# controller.net
KiCad netlist of a schematic drawn in EAGLE
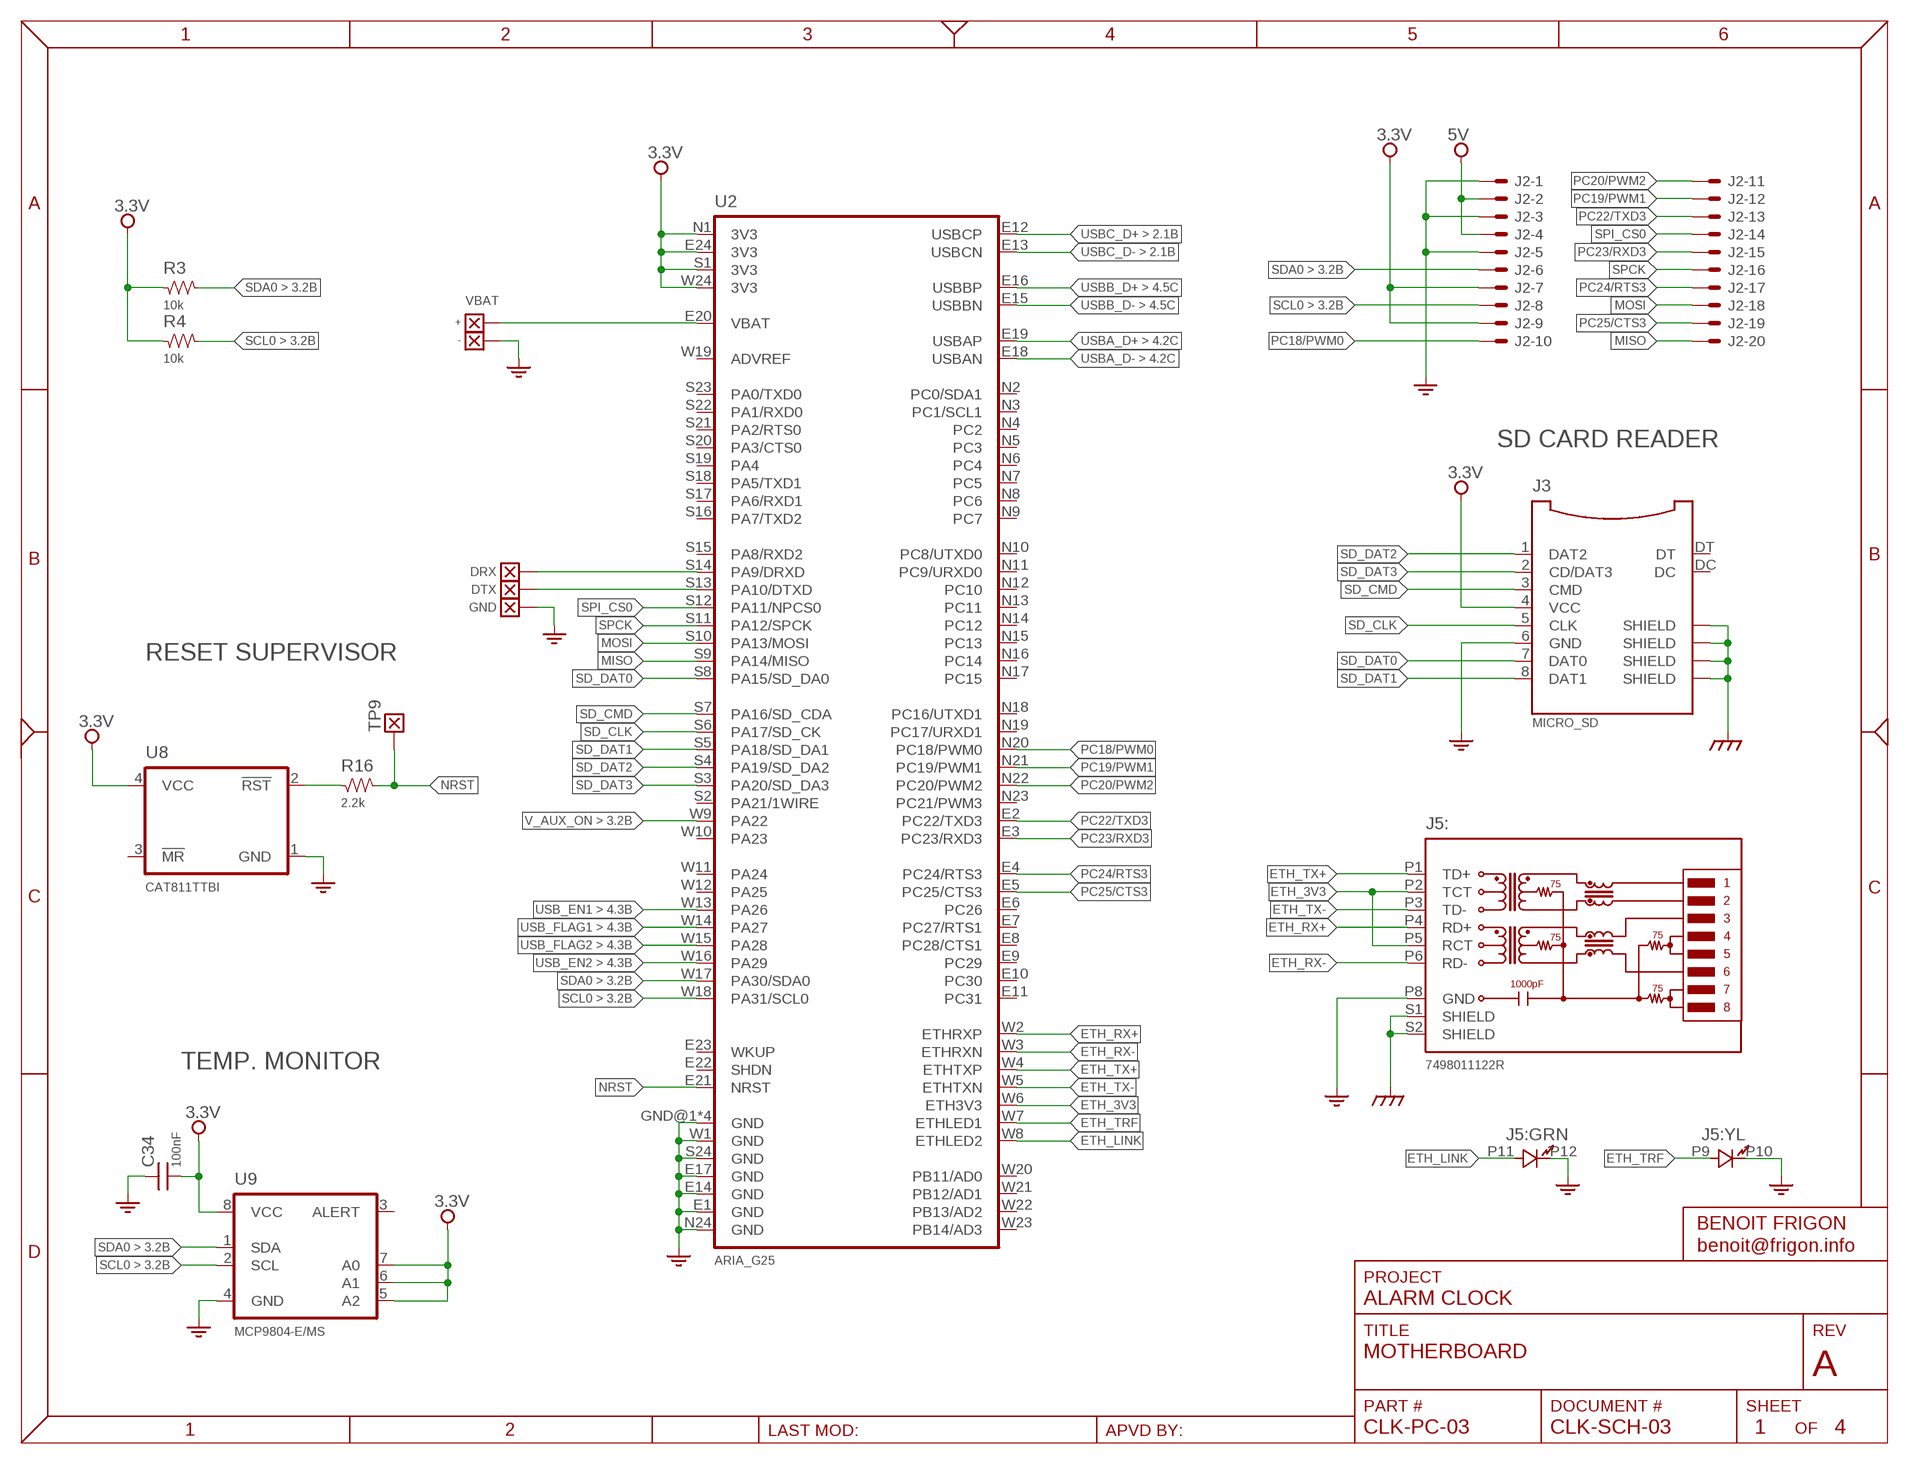
[diagram p0: schematic, sheet 1]
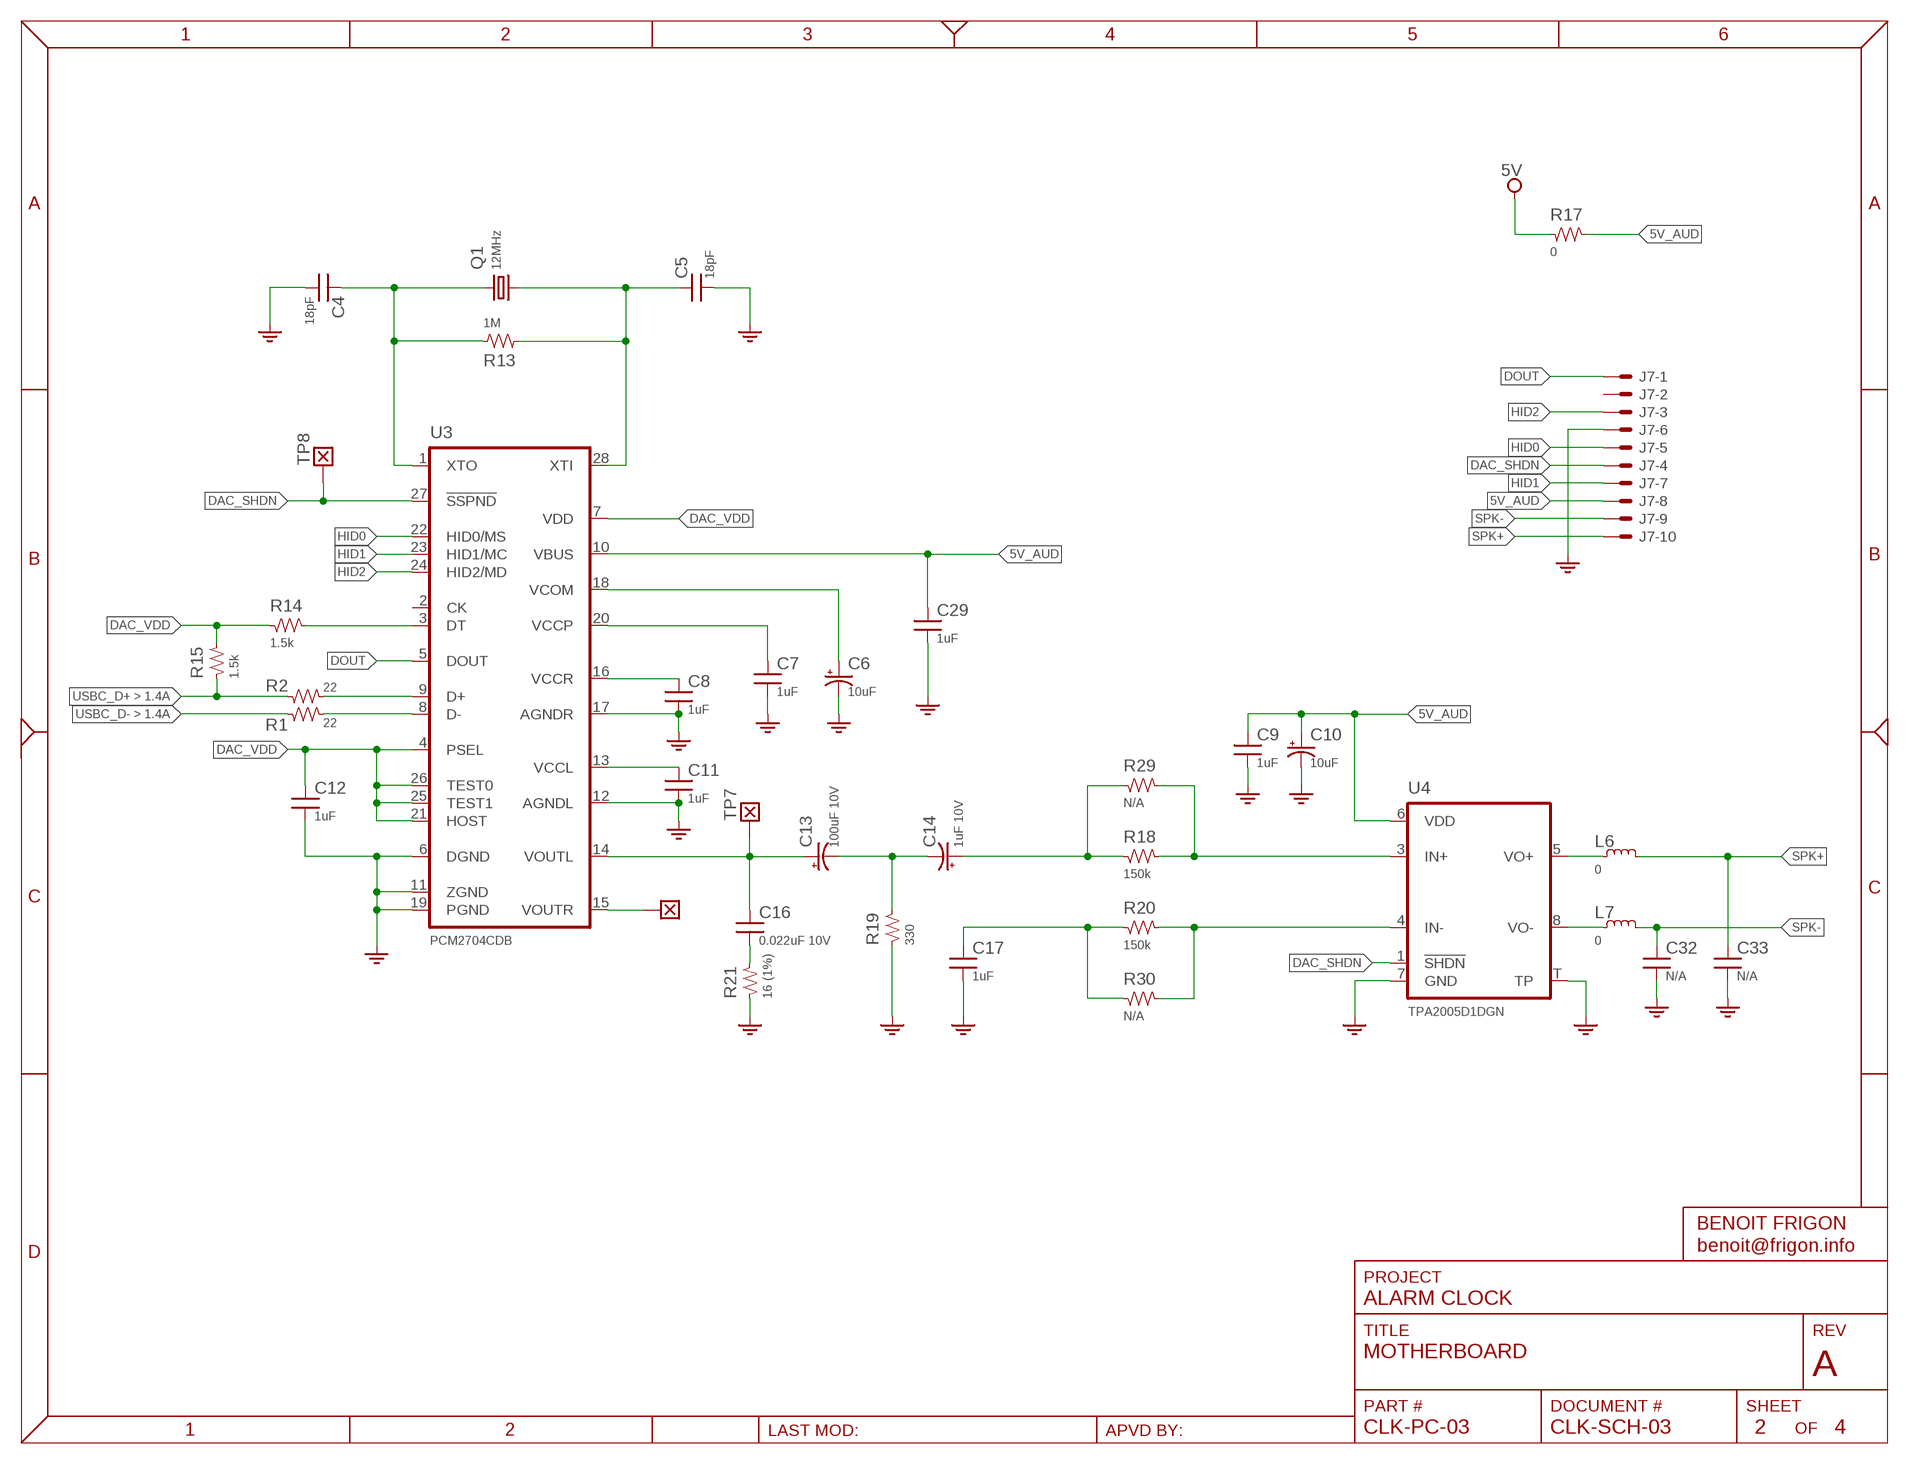
[diagram p1: schematic, sheet 2]
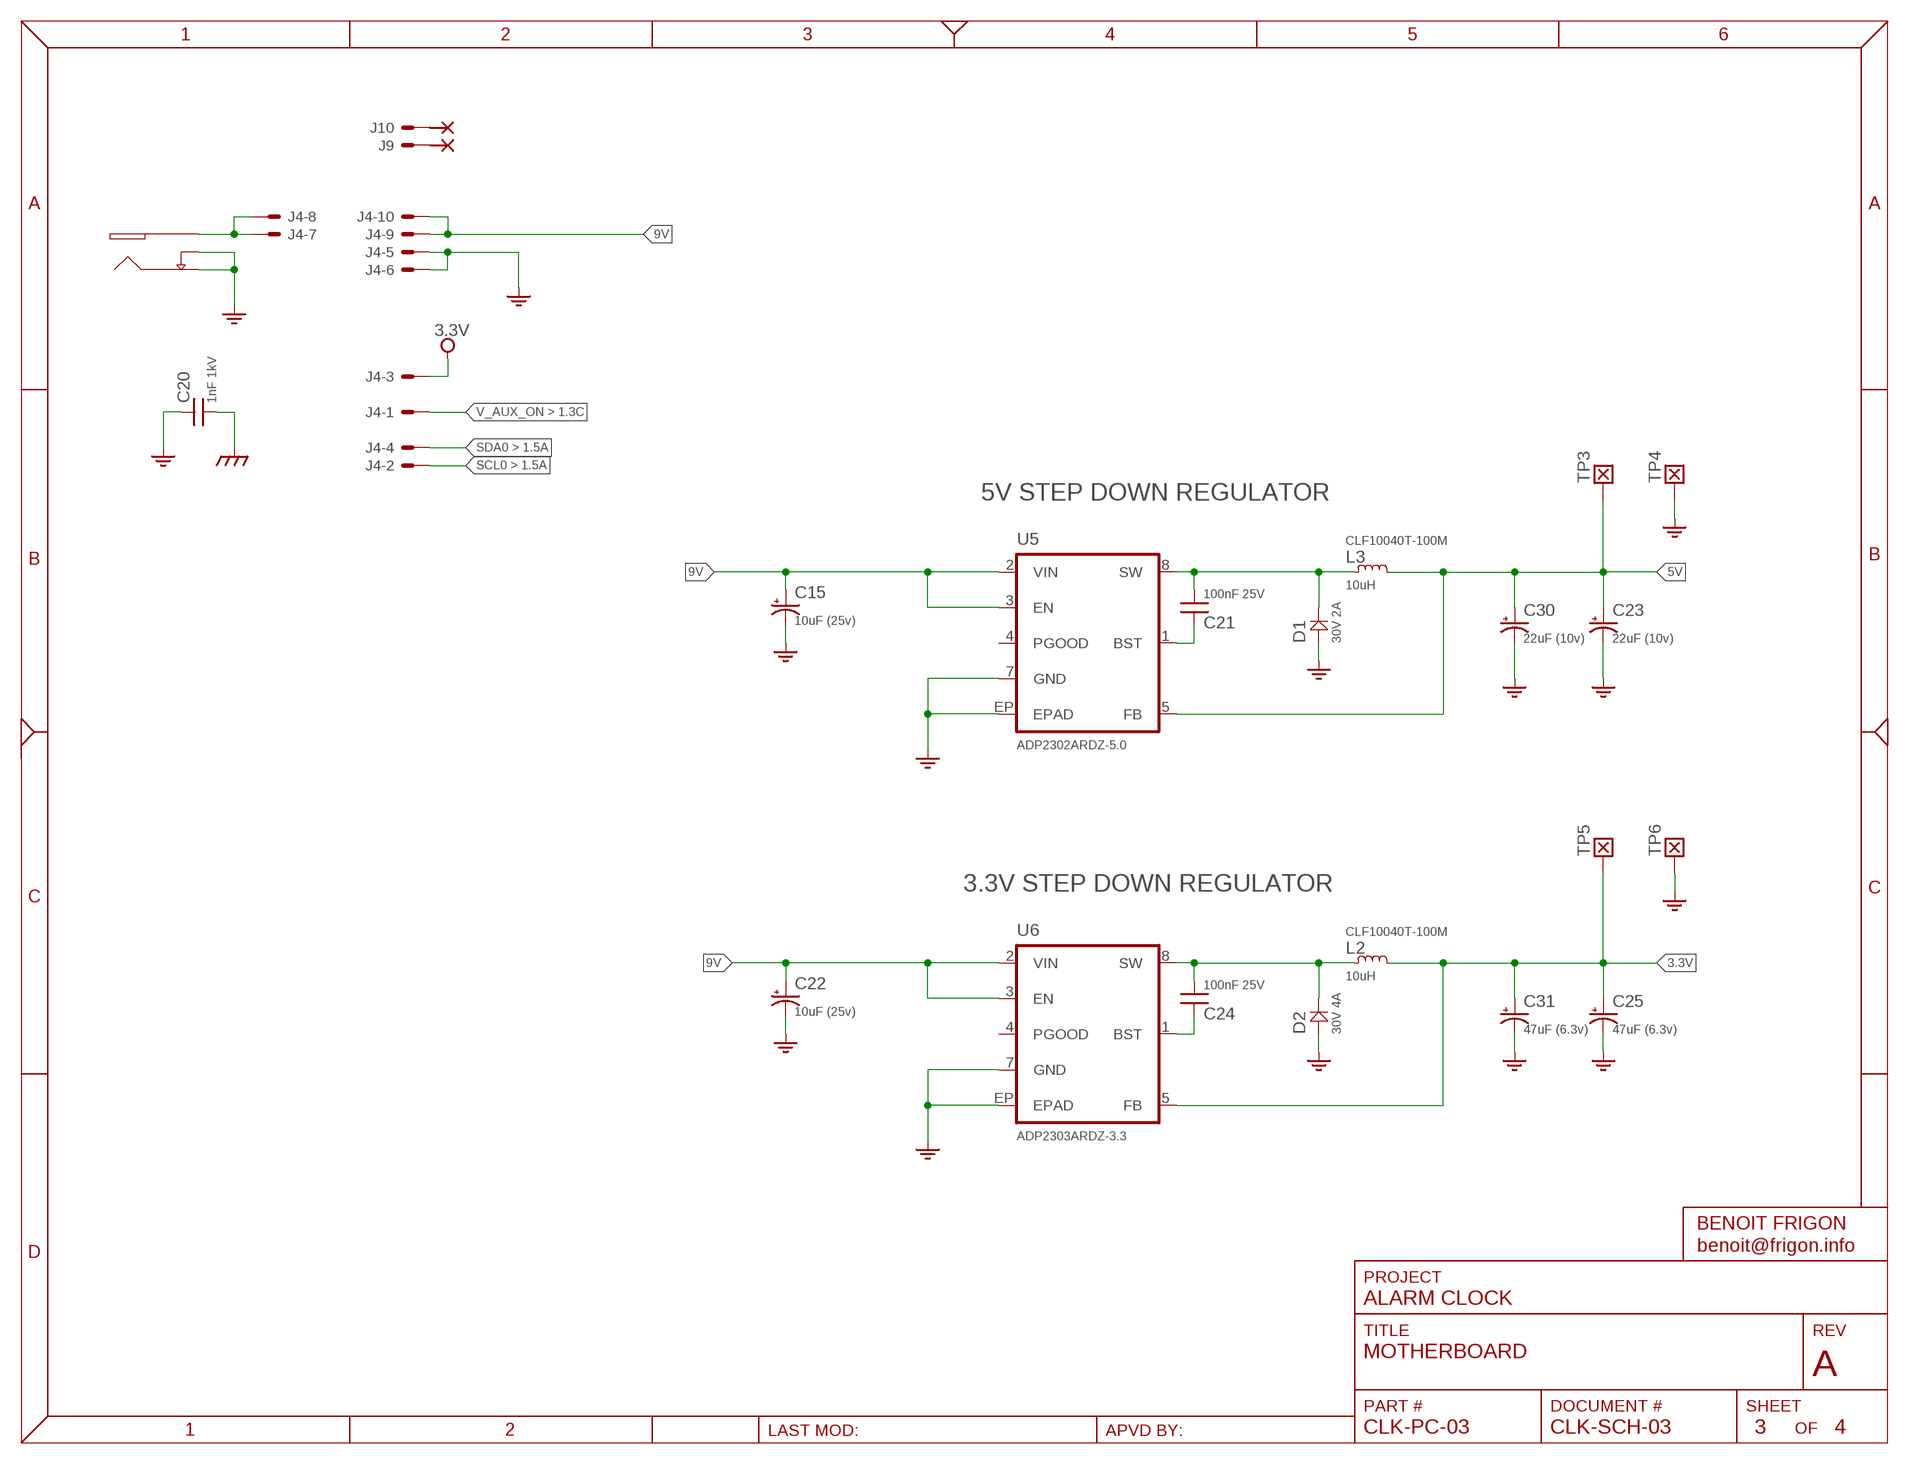
[diagram p2: schematic, sheet 3]
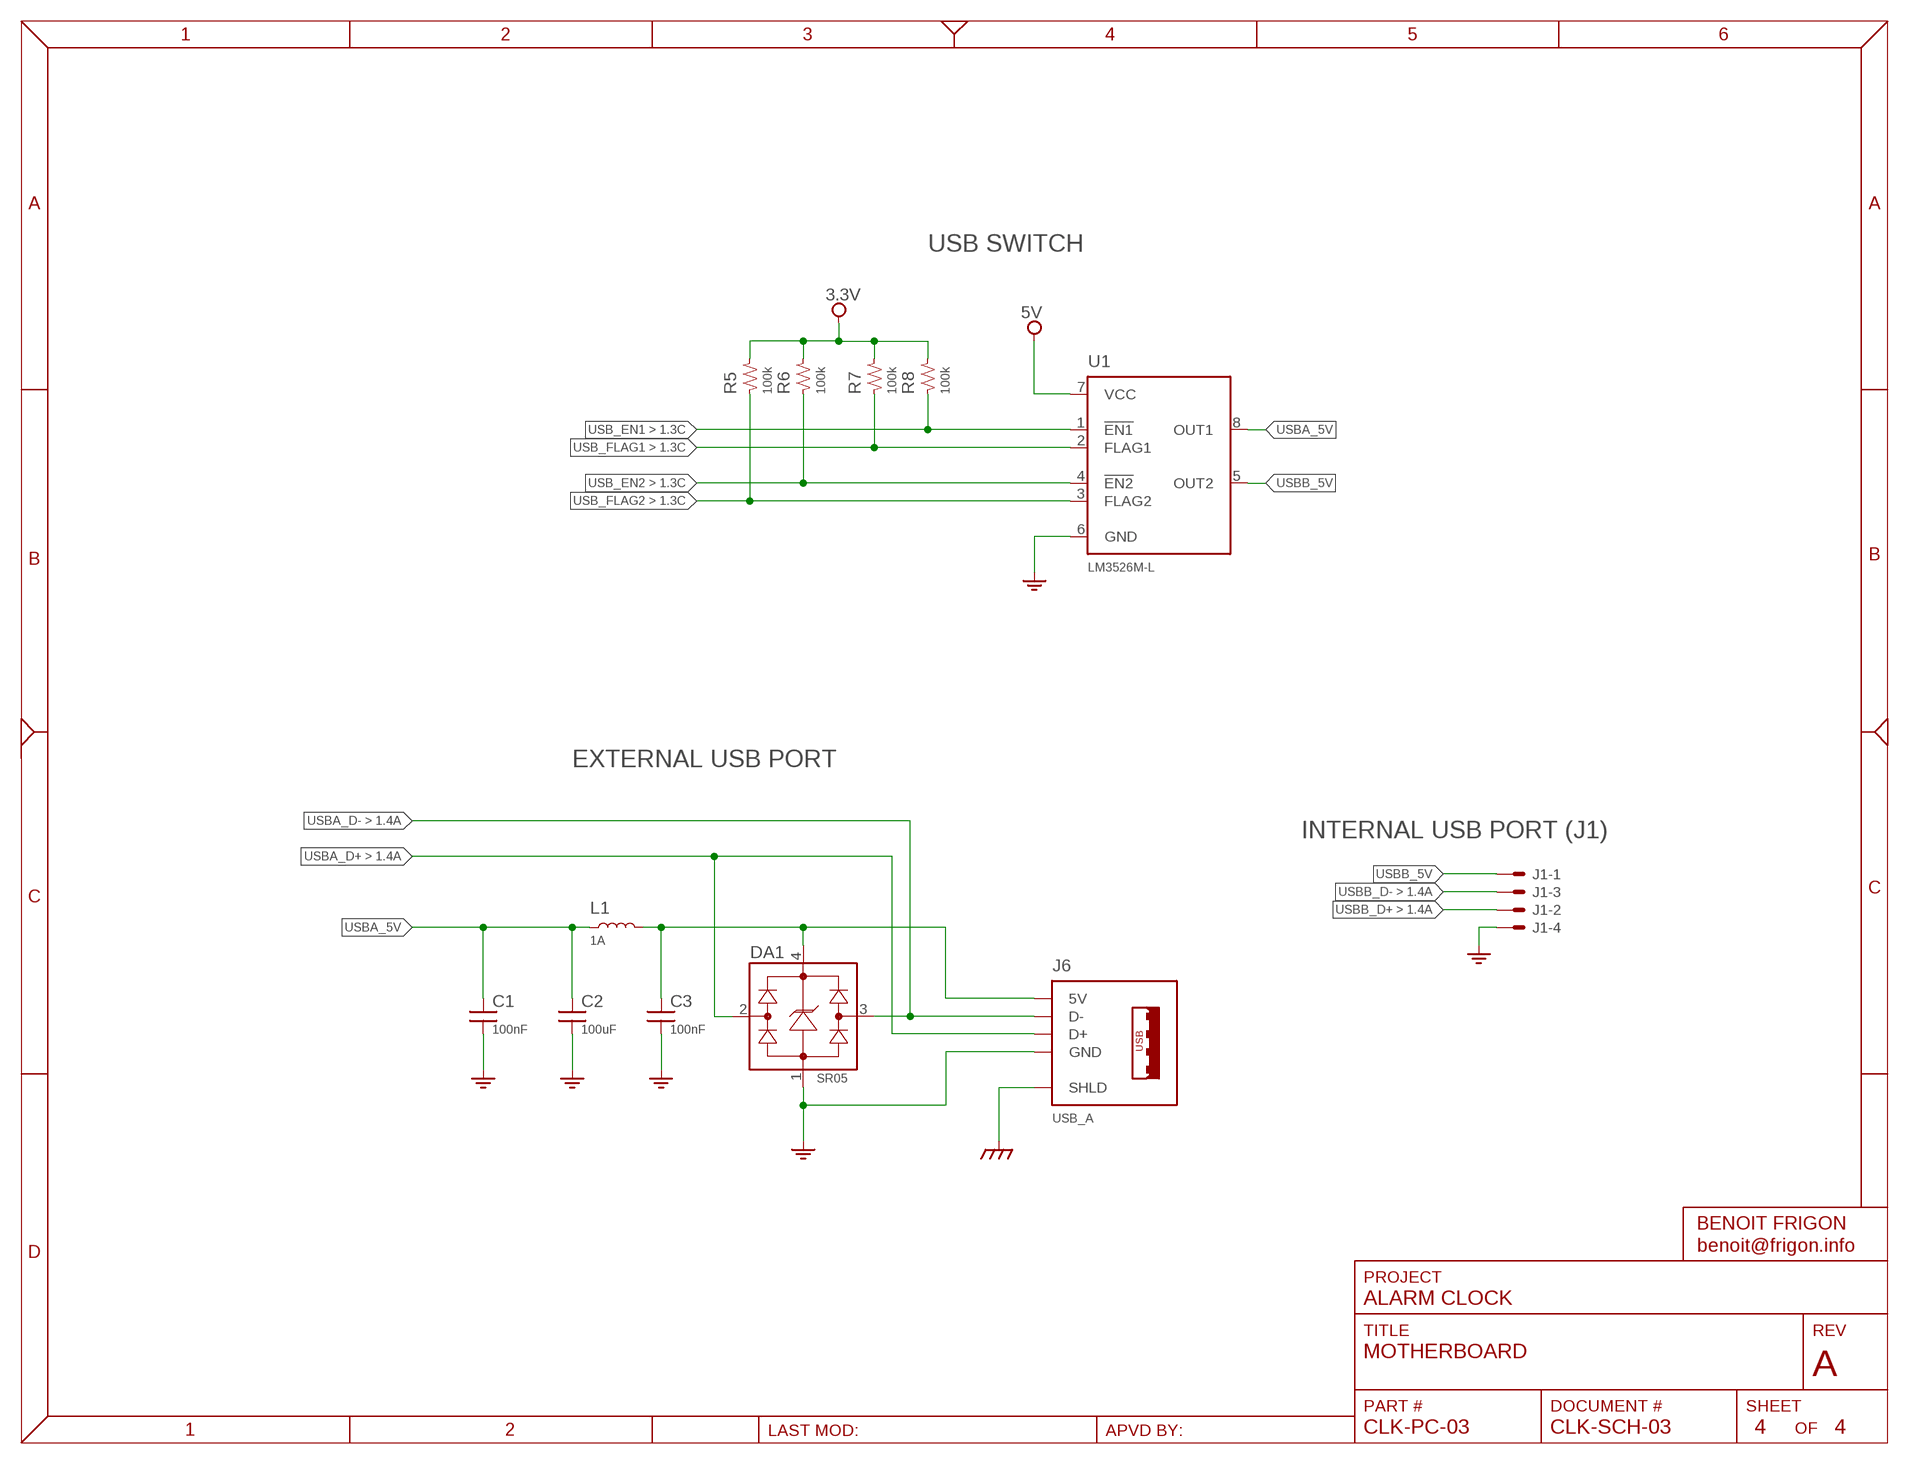
[diagram p3: schematic, sheet 4]

(export (version "E")
  (design (tool "Eeschema 10.0.6"))
  (components
    (comp (ref "C4")
      (value "18pF")
      (footprint "eagle-import:SMD_0603")
      (description "{DESCRIPTION} - SMT 0603 - {value}")
      (fields (field (name "PACKAGE") "SMT 0603"))
      (libsource (lib "eagle-import") (part "CAP-0603"))
    )
    (comp (ref "C5")
      (value "18pF")
      (footprint "eagle-import:SMD_0603")
      (libsource (lib "eagle-import") (part "CAP-0603"))
    )
    (comp (ref "C6")
      (value "10uF")
      (footprint "eagle-import:CAP_S0805")
      (description "Aluminium capacitor - SMT 0805 - {VALUE}")
      (libsource (lib "eagle-import") (part "CAP-E-?-0805ALUM"))
    )
    (comp (ref "C7")
      (value "1uF")
      (footprint "eagle-import:SMD_0603")
      (libsource (lib "eagle-import") (part "CAP-0603"))
    )
    (comp (ref "C8")
      (value "1uF")
      (footprint "eagle-import:SMD_0603")
      (description "{DESCRIPTION} - SMT 0603 - {value}")
      (fields (field (name "PACKAGE") "SMT 0603"))
      (libsource (lib "eagle-import") (part "CAP-0603"))
    )
    (comp (ref "C9")
      (value "1uF")
      (footprint "eagle-import:SMD_0603")
      (libsource (lib "eagle-import") (part "CAP-0603"))
    )
    (comp (ref "C10")
      (value "10uF")
      (footprint "eagle-import:CAP_S0805")
      (description "Aluminium capacitor - SMT 0805 - {VALUE}")
      (libsource (lib "eagle-import") (part "CAP-E-?-0805ALUM"))
    )
    (comp (ref "C11")
      (value "1uF")
      (footprint "eagle-import:SMD_0603")
      (description "{DESCRIPTION} - SMT 0603 - {value}")
      (fields (field (name "PACKAGE") "SMT 0603"))
      (libsource (lib "eagle-import") (part "CAP-0603"))
    )
    (comp (ref "C12")
      (value "1uF")
      (footprint "eagle-import:SMD_0603")
      (libsource (lib "eagle-import") (part "CAP-0603"))
    )
    (comp (ref "C13")
      (value "100uF 10V")
      (footprint "eagle-import:CAP_S1210")
      (description "Aluminium capacitor - SMT 1210 - {VALUE}")
      (fields (field (name "MFG") "AVX"))
      (libsource (lib "eagle-import") (part "CAP-E-?-1210ALUM"))
    )
    (comp (ref "C14")
      (value "1uF 10V")
      (footprint "eagle-import:CAP_S0805")
      (description "Aluminium capacitor - SMT 0805 - {VALUE}")
      (libsource (lib "eagle-import") (part "CAP-E-?-0805ALUM"))
    )
    (comp (ref "C16")
      (value "0.022uF 10V")
      (footprint "eagle-import:SMD_0603")
      (libsource (lib "eagle-import") (part "CAP-0603"))
    )
    (comp (ref "C17")
      (value "1uF")
      (footprint "eagle-import:SMD_0603")
      (libsource (lib "eagle-import") (part "CAP-0603"))
    )
    (comp (ref "C29")
      (value "1uF")
      (footprint "eagle-import:SMD_0603")
      (libsource (lib "eagle-import") (part "CAP-0603"))
    )
    (comp (ref "C32")
      (value "N/A")
      (footprint "eagle-import:SMD_0603")
      (libsource (lib "eagle-import") (part "CAP-0603"))
    )
    (comp (ref "C33")
      (value "N/A")
      (footprint "eagle-import:SMD_0603")
      (libsource (lib "eagle-import") (part "CAP-0603"))
    )
    (comp (ref "J7")
      (value "DL-1.25MM-HEADER-10")
      (footprint "eagle-import:DF13A-10DP-1.25")
      (libsource (lib "eagle-import") (part "DL-1.25MM-HEADER-10"))
    )
    (comp (ref "L6")
      (value "0")
      (footprint "eagle-import:SMD_0603")
      (description "{DESCRIPTION} - SMT 0603 - {VALUE}")
      (libsource (lib "eagle-import") (part "IND?-0603"))
    )
    (comp (ref "L7")
      (value "0")
      (footprint "eagle-import:SMD_0603")
      (description "{DESCRIPTION} - SMT 0603 - {VALUE}")
      (libsource (lib "eagle-import") (part "IND?-0603"))
    )
    (comp (ref "Q1")
      (value "12MHz")
      (footprint "eagle-import:HC49UP")
      (libsource (lib "eagle-import") (part "XTALHC49UP"))
    )
    (comp (ref "R1")
      (value "22")
      (footprint "eagle-import:SMD_0603")
      (libsource (lib "eagle-import") (part "RES-0603"))
    )
    (comp (ref "R2")
      (value "22")
      (footprint "eagle-import:SMD_0603")
      (libsource (lib "eagle-import") (part "RES-0603"))
    )
    (comp (ref "R13")
      (value "1M")
      (footprint "eagle-import:SMD_0603")
      (libsource (lib "eagle-import") (part "RES-0603"))
    )
    (comp (ref "R14")
      (value "1.5k")
      (footprint "eagle-import:SMD_0603")
      (libsource (lib "eagle-import") (part "RES-0603"))
    )
    (comp (ref "R15")
      (value "1.5k")
      (footprint "eagle-import:SMD_0603")
      (libsource (lib "eagle-import") (part "RES-0603"))
    )
    (comp (ref "R17")
      (value "0")
      (footprint "eagle-import:SMD_1206")
      (libsource (lib "eagle-import") (part "RES-1206"))
    )
    (comp (ref "R18")
      (value "150k")
      (footprint "eagle-import:SMD_0603")
      (libsource (lib "eagle-import") (part "RES-0603"))
    )
    (comp (ref "R19")
      (value "330")
      (footprint "eagle-import:SMD_0603")
      (libsource (lib "eagle-import") (part "RES-0603"))
    )
    (comp (ref "R20")
      (value "150k")
      (footprint "eagle-import:SMD_0603")
      (description "{DESCRIPTION} - SMT 0603 - {VALUE}")
      (fields (field (name "PACKAGE") "SMT 0603"))
      (libsource (lib "eagle-import") (part "RES-0603"))
    )
    (comp (ref "R21")
      (value "16 (1%)")
      (footprint "eagle-import:SMD_0603")
      (libsource (lib "eagle-import") (part "RES-0603"))
    )
    (comp (ref "R29")
      (value "N/A")
      (footprint "eagle-import:SMD_0603")
      (description "{DESCRIPTION} - SMT 0603 - {VALUE}")
      (fields (field (name "PACKAGE") "SMT 0603"))
      (libsource (lib "eagle-import") (part "RES-0603"))
    )
    (comp (ref "R30")
      (value "N/A")
      (footprint "eagle-import:SMD_0603")
      (description "{DESCRIPTION} - SMT 0603 - {VALUE}")
      (fields (field (name "PACKAGE") "SMT 0603"))
      (libsource (lib "eagle-import") (part "RES-0603"))
    )
    (comp (ref "TP7")
      (value "TEST_POINT-050")
      (footprint "eagle-import:TP_050")
      (libsource (lib "eagle-import") (part "TEST_POINT-050"))
    )
    (comp (ref "TP8")
      (value "TEST_POINT-050")
      (footprint "eagle-import:TP_050")
      (libsource (lib "eagle-import") (part "TEST_POINT-050"))
    )
    (comp (ref "U3")
      (value "PCM2704CDB")
      (footprint "eagle-import:SSOP28")
      (libsource (lib "eagle-import") (part "PCM2704CDB"))
    )
    (comp (ref "U4")
      (value "TPA2005D1DGN")
      (footprint "eagle-import:PPSOP8")
      (libsource (lib "eagle-import") (part "TPA2005D1?DGN"))
    )
    (comp (ref "W1")
      (value "WIRE-150X75")
      (footprint "eagle-import:WIRE_SMT_150X75")
      (libsource (lib "eagle-import") (part "WIRE-?150X75"))
    )
    (comp (ref "C15")
      (value "10uF (25v)")
      (footprint "eagle-import:CAP_S1210")
      (fields (field (name "MFG") "AVX") (field (name "PART_NO") "TPSB106K025R1800"))
      (libsource (lib "eagle-import") (part "CAP-E-?-1210TANT"))
    )
    (comp (ref "C20")
      (value "1nF 1kV")
      (footprint "eagle-import:SMD_0805")
      (libsource (lib "eagle-import") (part "CAP-0805"))
    )
    (comp (ref "C21")
      (value "100nF 25V")
      (footprint "eagle-import:SMD_0603")
      (libsource (lib "eagle-import") (part "CAP-0603"))
    )
    (comp (ref "C22")
      (value "10uF (25v)")
      (footprint "eagle-import:CAP_S1210")
      (fields (field (name "MFG") "AVX") (field (name "PART_NO") "TPSB106K025R1800"))
      (libsource (lib "eagle-import") (part "CAP-E-?-1210TANT"))
    )
    (comp (ref "C23")
      (value "22uF (10v)")
      (footprint "eagle-import:CAP_S1206")
      (description "Tantalum capacitor - SMT 1206 - {VALUE}")
      (fields (field (name "MFG") "AVX") (field (name "PART_NO") "TPSA226M010R0900"))
      (libsource (lib "eagle-import") (part "CAP-E-?-1206TANT"))
    )
    (comp (ref "C24")
      (value "100nF 25V")
      (footprint "eagle-import:SMD_0603")
      (libsource (lib "eagle-import") (part "CAP-0603"))
    )
    (comp (ref "C25")
      (value "47uF (6.3v)")
      (footprint "eagle-import:CAP_S1206")
      (description "Tantalum capacitor - SMT 1206 - {VALUE}")
      (fields (field (name "MFG") "AVX") (field (name "PART_NO") "TPSA476K006R0800"))
      (libsource (lib "eagle-import") (part "CAP-E-?-1206TANT"))
    )
    (comp (ref "C30")
      (value "22uF (10v)")
      (footprint "eagle-import:CAP_S1206")
      (description "Tantalum capacitor - SMT 1206 - {VALUE}")
      (fields (field (name "MFG") "AVX") (field (name "PART_NO") "TPSA226M010R0900"))
      (libsource (lib "eagle-import") (part "CAP-E-?-1206TANT"))
    )
    (comp (ref "C31")
      (value "47uF (6.3v)")
      (footprint "eagle-import:CAP_S1206")
      (description "Tantalum capacitor - SMT 1206 - {VALUE}")
      (fields (field (name "MFG") "AVX") (field (name "PART_NO") "TPSA476K006R0800"))
      (libsource (lib "eagle-import") (part "CAP-E-?-1206TANT"))
    )
    (comp (ref "D1")
      (value "30V 2A")
      (footprint "eagle-import:DIODE_DO214-AA")
      (libsource (lib "eagle-import") (part "DIODE-DO214-AA"))
    )
    (comp (ref "D2")
      (value "30V 4A")
      (footprint "eagle-import:DIODE_DO214-AA")
      (libsource (lib "eagle-import") (part "DIODE-DO214-AA"))
    )
    (comp (ref "J4")
      (value "DL-100-HEADER-10-V")
      (footprint "eagle-import:534206-5")
      (description "{DESCRIPTION} Receptacle - Vertical")
      (fields (field (name "MFG") "Tyco Electronics") (field (name "SKU") "534206-5"))
      (libsource (lib "eagle-import") (part "DL-100-HEADER-10-V"))
    )
    (comp (ref "J8")
      (value "CUI-PJ-013C")
      (footprint "eagle-import:CUI-PJ-013C")
      (libsource (lib "eagle-import") (part "CUI-PJ-013C"))
    )
    (comp (ref "J9")
      (value "SNG-100-HEADER-01-HDR-V")
      (footprint "eagle-import:HDR_M_1")
      (libsource (lib "eagle-import") (part "SNG-100-HEADER-01-HDR-V"))
    )
    (comp (ref "J10")
      (value "SNG-100-HEADER-01-HDR-V")
      (footprint "eagle-import:HDR_M_1")
      (libsource (lib "eagle-import") (part "SNG-100-HEADER-01-HDR-V"))
    )
    (comp (ref "L2")
      (value "10uH")
      (footprint "eagle-import:IND-10X10")
      (fields (field (name "PART_NO") "CLF10040T-100M"))
      (libsource (lib "eagle-import") (part "IND?-10X10"))
    )
    (comp (ref "L3")
      (value "10uH")
      (footprint "eagle-import:IND-10X10")
      (fields (field (name "MFG") "TDK") (field (name "PART_NO") "CLF10040T-100M"))
      (libsource (lib "eagle-import") (part "IND?-10X10"))
    )
    (comp (ref "TP3")
      (value "TEST_POINT-050")
      (footprint "eagle-import:TP_050")
      (libsource (lib "eagle-import") (part "TEST_POINT-050"))
    )
    (comp (ref "TP4")
      (value "TEST_POINT-050")
      (footprint "eagle-import:TP_050")
      (libsource (lib "eagle-import") (part "TEST_POINT-050"))
    )
    (comp (ref "TP5")
      (value "TEST_POINT-050")
      (footprint "eagle-import:TP_050")
      (fields (field (name "BOM") "FALSE"))
      (libsource (lib "eagle-import") (part "TEST_POINT-050"))
    )
    (comp (ref "TP6")
      (value "TEST_POINT-050")
      (footprint "eagle-import:TP_050")
      (fields (field (name "BOM") "FALSE"))
      (libsource (lib "eagle-import") (part "TEST_POINT-050"))
    )
    (comp (ref "U5")
      (value "ADP2302ARDZ-5.0")
      (footprint "eagle-import:SOIC8-EP")
      (description "{DESCRIPTION} - 2A, 5V")
      (fields (field (name "MFG") "Analog Devices"))
      (libsource (lib "eagle-import") (part "ADP230?2ARDZ-5.0"))
    )
    (comp (ref "U6")
      (value "ADP2303ARDZ-3.3")
      (footprint "eagle-import:SOIC8-EP")
      (description "{DESCRIPTION} - 3A, 3.3v")
      (fields (field (name "MFG") "Analog Devices"))
      (libsource (lib "eagle-import") (part "ADP230?3ARDZ-3.3"))
    )
    (comp (ref "C34")
      (value "100nF")
      (footprint "eagle-import:SMD_0603")
      (libsource (lib "eagle-import") (part "CAP-0603"))
    )
    (comp (ref "J2")
      (value "DL-1.25MM-HEADER-20")
      (footprint "eagle-import:DF13A-20DP-1.25")
      (libsource (lib "eagle-import") (part "DL-1.25MM-HEADER-20"))
    )
    (comp (ref "J3")
      (value "MICRO_SD")
      (footprint "eagle-import:5027020891")
      (libsource (lib "eagle-import") (part "MICRO_SD"))
    )
    (comp (ref "J5")
      (value "7498011122R")
      (footprint "eagle-import:7498011122R")
      (libsource (lib "eagle-import") (part "7498011122R"))
    )
    (comp (ref "R3")
      (value "10k")
      (footprint "eagle-import:SMD_0603")
      (description "{DESCRIPTION} - SMT 0603 - {VALUE}")
      (fields (field (name "PACKAGE") "SMT 0603"))
      (libsource (lib "eagle-import") (part "RES-0603"))
    )
    (comp (ref "R4")
      (value "10k")
      (footprint "eagle-import:SMD_0603")
      (description "{DESCRIPTION} - SMT 0603 - {VALUE}")
      (fields (field (name "PACKAGE") "SMT 0603"))
      (libsource (lib "eagle-import") (part "RES-0603"))
    )
    (comp (ref "R16")
      (value "2.2k")
      (footprint "eagle-import:SMD_0603")
      (libsource (lib "eagle-import") (part "RES-0603"))
    )
    (comp (ref "TP1")
      (value "+")
      (footprint "eagle-import:WIRE_SMT_150X75")
      (libsource (lib "eagle-import") (part "WIRE-?150X75"))
    )
    (comp (ref "TP2")
      (value "-")
      (footprint "eagle-import:WIRE_SMT_150X75")
      (libsource (lib "eagle-import") (part "WIRE-?150X75"))
    )
    (comp (ref "TP9")
      (value "TEST_POINT-050")
      (footprint "eagle-import:TP_050")
      (libsource (lib "eagle-import") (part "TEST_POINT-050"))
    )
    (comp (ref "U2")
      (value "ARIA_G25")
      (footprint "eagle-import:ARIA_G25")
      (libsource (lib "eagle-import") (part "ARIA_G25"))
    )
    (comp (ref "U8")
      (value "CAT811TTBI")
      (footprint "eagle-import:SOT143")
      (description "{DESCRIPTION} - 3.08V threshold")
      (fields (field (name "MFG") "ON Semiconductors"))
      (libsource (lib "eagle-import") (part "CAT811?TBIT"))
    )
    (comp (ref "U9")
      (value "MCP9804-E/MS")
      (footprint "eagle-import:MSOP8")
      (fields (field (name "MFG") "Microchip"))
      (libsource (lib "eagle-import") (part "MCP9804-/?MSE"))
    )
    (comp (ref "W2")
      (value "DRX")
      (footprint "eagle-import:WIRE_SMT_150X75")
      (libsource (lib "eagle-import") (part "WIRE-?150X75"))
    )
    (comp (ref "W3")
      (value "DTX")
      (footprint "eagle-import:WIRE_SMT_150X75")
      (libsource (lib "eagle-import") (part "WIRE-?150X75"))
    )
    (comp (ref "W4")
      (value "GND")
      (footprint "eagle-import:WIRE_SMT_150X75")
      (libsource (lib "eagle-import") (part "WIRE-?150X75"))
    )
    (comp (ref "C1")
      (value "100nF")
      (footprint "eagle-import:SMD_0603")
      (libsource (lib "eagle-import") (part "CAP-0603"))
    )
    (comp (ref "C2")
      (value "100uF")
      (footprint "eagle-import:SMD_0805")
      (libsource (lib "eagle-import") (part "CAP-0805"))
    )
    (comp (ref "C3")
      (value "100nF")
      (footprint "eagle-import:SMD_0603")
      (libsource (lib "eagle-import") (part "CAP-0603"))
    )
    (comp (ref "DA1")
      (value "SR05")
      (footprint "eagle-import:SOT143")
      (fields (field (name "MFG") "Semtech"))
      (libsource (lib "eagle-import") (part "SR05"))
    )
    (comp (ref "J1")
      (value "SNG-2MM-HEADER-04-V")
      (footprint "eagle-import:DF3X-4P-2DSA")
      (description "{DESCRIPTION} - Vertical")
      (fields (field (name "MFG") "Hirose Electronic") (field (name "SKU") "DF3A-4P-2DSA"))
      (libsource (lib "eagle-import") (part "SNG-2MM-HEADER-04-V"))
    )
    (comp (ref "J6")
      (value "USB_A")
      (footprint "eagle-import:292303-1")
      (libsource (lib "eagle-import") (part "USB_A"))
    )
    (comp (ref "L1")
      (value "1A")
      (footprint "eagle-import:SMD_0805")
      (libsource (lib "eagle-import") (part "FERRITE"))
    )
    (comp (ref "R5")
      (value "100k")
      (footprint "eagle-import:SMD_0603")
      (description "{DESCRIPTION} - SMT 0603 - {VALUE}")
      (fields (field (name "PACKAGE") "SMT 0603"))
      (libsource (lib "eagle-import") (part "RES-0603"))
    )
    (comp (ref "R6")
      (value "100k")
      (footprint "eagle-import:SMD_0603")
      (description "{DESCRIPTION} - SMT 0603 - {VALUE}")
      (fields (field (name "PACKAGE") "SMT 0603"))
      (libsource (lib "eagle-import") (part "RES-0603"))
    )
    (comp (ref "R7")
      (value "100k")
      (footprint "eagle-import:SMD_0603")
      (description "{DESCRIPTION} - SMT 0603 - {VALUE}")
      (fields (field (name "PACKAGE") "SMT 0603"))
      (libsource (lib "eagle-import") (part "RES-0603"))
    )
    (comp (ref "R8")
      (value "100k")
      (footprint "eagle-import:SMD_0603")
      (description "{DESCRIPTION} - SMT 0603 - {VALUE}")
      (fields (field (name "PACKAGE") "SMT 0603"))
      (libsource (lib "eagle-import") (part "RES-0603"))
    )
    (comp (ref "U1")
      (value "LM3526M-L")
      (footprint "eagle-import:SOIC8")
      (fields (field (name "MFG") "National Semiconductors"))
      (libsource (lib "eagle-import") (part "LM3526?-ML"))
    )
  )
  (nets
    (net (code "1") (name "3.3V") (class "Default")
      (node (ref "C25") (pin "+") (pinfunction "+_+") (pintype "passive"))
      (node (ref "C31") (pin "+") (pinfunction "+_+") (pintype "passive"))
      (node (ref "C34") (pin "2") (pinfunction "2_2") (pintype "passive"))
      (node (ref "J2") (pin "7") (pinfunction "S_7") (pintype "bidirectional"))
      (node (ref "J2") (pin "9") (pinfunction "S_9") (pintype "bidirectional"))
      (node (ref "J3") (pin "4") (pinfunction "VCC_4") (pintype "power_in"))
      (node (ref "J4") (pin "3") (pinfunction "S_3") (pintype "bidirectional"))
      (node (ref "L2") (pin "2") (pinfunction "2_2") (pintype "passive"))
      (node (ref "R3") (pin "1") (pinfunction "1_1") (pintype "passive"))
      (node (ref "R4") (pin "1") (pinfunction "1_1") (pintype "passive"))
      (node (ref "R5") (pin "2") (pinfunction "2_2") (pintype "passive"))
      (node (ref "R6") (pin "2") (pinfunction "2_2") (pintype "passive"))
      (node (ref "R7") (pin "2") (pinfunction "2_2") (pintype "passive"))
      (node (ref "R8") (pin "2") (pinfunction "2_2") (pintype "passive"))
      (node (ref "TP5") (pin "1") (pinfunction "P$1_1") (pintype "bidirectional"))
      (node (ref "U2") (pin "E24") (pinfunction "3V3_E24") (pintype "power_in"))
      (node (ref "U2") (pin "N1") (pinfunction "3V3_N1") (pintype "power_in"))
      (node (ref "U2") (pin "S1") (pinfunction "3V3_S1") (pintype "power_in"))
      (node (ref "U2") (pin "W24") (pinfunction "3V3_W24") (pintype "power_in"))
      (node (ref "U6") (pin "5") (pinfunction "FB_5") (pintype "bidirectional"))
      (node (ref "U8") (pin "4") (pinfunction "VCC_4") (pintype "power_in"))
      (node (ref "U9") (pin "5") (pinfunction "A2_5") (pintype "bidirectional"))
      (node (ref "U9") (pin "6") (pinfunction "A1_6") (pintype "bidirectional"))
      (node (ref "U9") (pin "7") (pinfunction "A0_7") (pintype "bidirectional"))
      (node (ref "U9") (pin "8") (pinfunction "VCC_8") (pintype "power_in"))
    )
    (net (code "2") (name "5V") (class "Default")
      (node (ref "C23") (pin "+") (pinfunction "+_+") (pintype "passive"))
      (node (ref "C30") (pin "+") (pinfunction "+_+") (pintype "passive"))
      (node (ref "J2") (pin "2") (pinfunction "S_2") (pintype "bidirectional"))
      (node (ref "J2") (pin "4") (pinfunction "S_4") (pintype "bidirectional"))
      (node (ref "L3") (pin "2") (pinfunction "2_2") (pintype "passive"))
      (node (ref "R17") (pin "1") (pinfunction "1_1") (pintype "passive"))
      (node (ref "TP3") (pin "1") (pinfunction "P$1_1") (pintype "bidirectional"))
      (node (ref "U1") (pin "7") (pinfunction "VCC_7") (pintype "bidirectional"))
      (node (ref "U5") (pin "5") (pinfunction "FB_5") (pintype "bidirectional"))
    )
    (net (code "3") (name "5V_AUD") (class "Default")
      (node (ref "C10") (pin "+") (pinfunction "+_+") (pintype "passive"))
      (node (ref "C29") (pin "1") (pinfunction "1_1") (pintype "passive"))
      (node (ref "C9") (pin "1") (pinfunction "1_1") (pintype "passive"))
      (node (ref "J7") (pin "8") (pinfunction "S_8") (pintype "bidirectional"))
      (node (ref "R17") (pin "2") (pinfunction "2_2") (pintype "passive"))
      (node (ref "U3") (pin "10") (pinfunction "VBUS_10") (pintype "bidirectional"))
      (node (ref "U4") (pin "6") (pinfunction "VDD_6") (pintype "bidirectional"))
    )
    (net (code "4") (name "9V") (class "Default")
      (node (ref "C15") (pin "+") (pinfunction "+_+") (pintype "passive"))
      (node (ref "C22") (pin "+") (pinfunction "+_+") (pintype "passive"))
      (node (ref "J4") (pin "10") (pinfunction "S_10") (pintype "bidirectional"))
      (node (ref "J4") (pin "9") (pinfunction "S_9") (pintype "bidirectional"))
      (node (ref "U5") (pin "2") (pinfunction "VIN_2") (pintype "bidirectional"))
      (node (ref "U5") (pin "3") (pinfunction "EN_3") (pintype "bidirectional"))
      (node (ref "U6") (pin "2") (pinfunction "VIN_2") (pintype "bidirectional"))
      (node (ref "U6") (pin "3") (pinfunction "EN_3") (pintype "bidirectional"))
    )
    (net (code "5") (name "DAC_SHDN") (class "Default")
      (node (ref "J7") (pin "4") (pinfunction "S_4") (pintype "bidirectional"))
      (node (ref "TP8") (pin "1") (pinfunction "P$1_1") (pintype "bidirectional"))
      (node (ref "U3") (pin "27") (pinfunction "~{SSPND}_27") (pintype "bidirectional"))
      (node (ref "U4") (pin "1") (pinfunction "~{SHDN}_1") (pintype "bidirectional"))
    )
    (net (code "6") (name "DAC_VDD") (class "Default")
      (node (ref "C12") (pin "1") (pinfunction "1_1") (pintype "passive"))
      (node (ref "R14") (pin "1") (pinfunction "1_1") (pintype "passive"))
      (node (ref "R15") (pin "2") (pinfunction "2_2") (pintype "passive"))
      (node (ref "U3") (pin "21") (pinfunction "HOST_21") (pintype "bidirectional"))
      (node (ref "U3") (pin "25") (pinfunction "TEST1_25") (pintype "bidirectional"))
      (node (ref "U3") (pin "26") (pinfunction "TEST0_26") (pintype "bidirectional"))
      (node (ref "U3") (pin "4") (pinfunction "PSEL_4") (pintype "bidirectional"))
      (node (ref "U3") (pin "7") (pinfunction "VDD_7") (pintype "bidirectional"))
    )
    (net (code "7") (name "DOUT") (class "Default")
      (node (ref "J7") (pin "1") (pinfunction "S_1") (pintype "bidirectional"))
      (node (ref "U3") (pin "5") (pinfunction "DOUT_5") (pintype "bidirectional"))
    )
    (net (code "8") (name "EARTH") (class "Default")
      (node (ref "C20") (pin "2") (pinfunction "2_2") (pintype "passive"))
      (node (ref "J3") (pin "SHDL@3") (pinfunction "SHIELD_SHDL@3") (pintype "power_in"))
      (node (ref "J3") (pin "SHLD@1") (pinfunction "SHIELD_SHLD@1") (pintype "power_in"))
      (node (ref "J3") (pin "SHLD@2") (pinfunction "SHIELD_SHLD@2") (pintype "power_in"))
      (node (ref "J3") (pin "SHLD@4") (pinfunction "SHIELD_SHLD@4") (pintype "power_in"))
      (node (ref "J5") (pin "S1") (pinfunction "SHIELD_S1") (pintype "bidirectional"))
      (node (ref "J5") (pin "S2") (pinfunction "SHIELD_S2") (pintype "bidirectional"))
      (node (ref "J6") (pin "SHLD@1") (pinfunction "SHLD_SHLD@1") (pintype "bidirectional"))
      (node (ref "J6") (pin "SHLD@2") (pinfunction "SHLD_SHLD@2") (pintype "bidirectional"))
    )
    (net (code "9") (name "ETH_3V3") (class "Default")
      (node (ref "J5") (pin "P2") (pinfunction "TCT_P2") (pintype "bidirectional"))
      (node (ref "J5") (pin "P5") (pinfunction "RCT_P5") (pintype "bidirectional"))
      (node (ref "U2") (pin "W6") (pinfunction "ETH3V3_W6") (pintype "bidirectional"))
    )
    (net (code "10") (name "ETH_LINK") (class "Default")
      (node (ref "J5") (pin "P11") (pinfunction "A_P11") (pintype "bidirectional"))
      (node (ref "U2") (pin "W8") (pinfunction "ETHLED2_W8") (pintype "bidirectional"))
    )
    (net (code "11") (name "ETH_RX+") (class "Default")
      (node (ref "J5") (pin "P4") (pinfunction "RD+_P4") (pintype "bidirectional"))
      (node (ref "U2") (pin "W2") (pinfunction "ETHRXP_W2") (pintype "bidirectional"))
    )
    (net (code "12") (name "ETH_RX-") (class "Default")
      (node (ref "J5") (pin "P6") (pinfunction "RD-_P6") (pintype "bidirectional"))
      (node (ref "U2") (pin "W3") (pinfunction "ETHRXN_W3") (pintype "bidirectional"))
    )
    (net (code "13") (name "ETH_TRF") (class "Default")
      (node (ref "J5") (pin "P9") (pinfunction "A_P9") (pintype "bidirectional"))
      (node (ref "U2") (pin "W7") (pinfunction "ETHLED1_W7") (pintype "bidirectional"))
    )
    (net (code "14") (name "ETH_TX+") (class "Default")
      (node (ref "J5") (pin "P1") (pinfunction "TD+_P1") (pintype "bidirectional"))
      (node (ref "U2") (pin "W4") (pinfunction "ETHTXP_W4") (pintype "bidirectional"))
    )
    (net (code "15") (name "ETH_TX-") (class "Default")
      (node (ref "J5") (pin "P3") (pinfunction "TD-_P3") (pintype "bidirectional"))
      (node (ref "U2") (pin "W5") (pinfunction "ETHTXN_W5") (pintype "bidirectional"))
    )
    (net (code "16") (name "GND") (class "Default")
      (node (ref "C1") (pin "2") (pinfunction "2_2") (pintype "passive"))
      (node (ref "C10") (pin "-") (pinfunction "-_-") (pintype "passive"))
      (node (ref "C11") (pin "2") (pinfunction "2_2") (pintype "passive"))
      (node (ref "C12") (pin "2") (pinfunction "2_2") (pintype "passive"))
      (node (ref "C15") (pin "-") (pinfunction "-_-") (pintype "passive"))
      (node (ref "C17") (pin "2") (pinfunction "2_2") (pintype "passive"))
      (node (ref "C2") (pin "2") (pinfunction "2_2") (pintype "passive"))
      (node (ref "C20") (pin "1") (pinfunction "1_1") (pintype "passive"))
      (node (ref "C22") (pin "-") (pinfunction "-_-") (pintype "passive"))
      (node (ref "C23") (pin "-") (pinfunction "-_-") (pintype "passive"))
      (node (ref "C25") (pin "-") (pinfunction "-_-") (pintype "passive"))
      (node (ref "C29") (pin "2") (pinfunction "2_2") (pintype "passive"))
      (node (ref "C3") (pin "2") (pinfunction "2_2") (pintype "passive"))
      (node (ref "C30") (pin "-") (pinfunction "-_-") (pintype "passive"))
      (node (ref "C31") (pin "-") (pinfunction "-_-") (pintype "passive"))
      (node (ref "C32") (pin "2") (pinfunction "2_2") (pintype "passive"))
      (node (ref "C33") (pin "2") (pinfunction "2_2") (pintype "passive"))
      (node (ref "C34") (pin "1") (pinfunction "1_1") (pintype "passive"))
      (node (ref "C4") (pin "2") (pinfunction "2_2") (pintype "passive"))
      (node (ref "C5") (pin "2") (pinfunction "2_2") (pintype "passive"))
      (node (ref "C6") (pin "-") (pinfunction "-_-") (pintype "passive"))
      (node (ref "C7") (pin "2") (pinfunction "2_2") (pintype "passive"))
      (node (ref "C8") (pin "2") (pinfunction "2_2") (pintype "passive"))
      (node (ref "C9") (pin "2") (pinfunction "2_2") (pintype "passive"))
      (node (ref "D1") (pin "A") (pinfunction "A_A") (pintype "passive"))
      (node (ref "D2") (pin "A") (pinfunction "A_A") (pintype "passive"))
      (node (ref "DA1") (pin "1") (pinfunction "1_1") (pintype "passive"))
      (node (ref "J1") (pin "4") (pinfunction "S_4") (pintype "bidirectional"))
      (node (ref "J2") (pin "1") (pinfunction "S_1") (pintype "bidirectional"))
      (node (ref "J2") (pin "3") (pinfunction "S_3") (pintype "bidirectional"))
      (node (ref "J2") (pin "5") (pinfunction "S_5") (pintype "bidirectional"))
      (node (ref "J3") (pin "6") (pinfunction "GND_6") (pintype "power_in"))
      (node (ref "J4") (pin "5") (pinfunction "S_5") (pintype "bidirectional"))
      (node (ref "J4") (pin "6") (pinfunction "S_6") (pintype "bidirectional"))
      (node (ref "J5") (pin "P10") (pinfunction "K_P10") (pintype "bidirectional"))
      (node (ref "J5") (pin "P12") (pinfunction "K_P12") (pintype "bidirectional"))
      (node (ref "J5") (pin "P8") (pinfunction "GND_P8") (pintype "bidirectional"))
      (node (ref "J6") (pin "4") (pinfunction "GND_4") (pintype "power_in"))
      (node (ref "J7") (pin "6") (pinfunction "S_6") (pintype "bidirectional"))
      (node (ref "J8") (pin "2") (pinfunction "GND_2") (pintype "bidirectional"))
      (node (ref "J8") (pin "3") (pinfunction "SW_3") (pintype "bidirectional"))
      (node (ref "R19") (pin "1") (pinfunction "1_1") (pintype "passive"))
      (node (ref "R21") (pin "1") (pinfunction "1_1") (pintype "passive"))
      (node (ref "TP2") (pin "1") (pinfunction "P$1_1") (pintype "bidirectional"))
      (node (ref "TP4") (pin "1") (pinfunction "P$1_1") (pintype "bidirectional"))
      (node (ref "TP6") (pin "1") (pinfunction "P$1_1") (pintype "bidirectional"))
      (node (ref "U1") (pin "6") (pinfunction "GND_6") (pintype "bidirectional"))
      (node (ref "U2") (pin "E1") (pinfunction "GND_E1") (pintype "power_in"))
      (node (ref "U2") (pin "E14") (pinfunction "GND_E14") (pintype "power_in"))
      (node (ref "U2") (pin "E17") (pinfunction "GND_E17") (pintype "power_in"))
      (node (ref "U2") (pin "GND@1") (pinfunction "GND_GND@1") (pintype "power_in"))
      (node (ref "U2") (pin "GND@2") (pinfunction "GND_GND@2") (pintype "power_in"))
      (node (ref "U2") (pin "GND@3") (pinfunction "GND_GND@3") (pintype "power_in"))
      (node (ref "U2") (pin "GND@4") (pinfunction "GND_GND@4") (pintype "power_in"))
      (node (ref "U2") (pin "N24") (pinfunction "GND_N24") (pintype "power_in"))
      (node (ref "U2") (pin "S24") (pinfunction "GND_S24") (pintype "power_in"))
      (node (ref "U2") (pin "W1") (pinfunction "GND_W1") (pintype "power_in"))
      (node (ref "U3") (pin "11") (pinfunction "ZGND_11") (pintype "bidirectional"))
      (node (ref "U3") (pin "12") (pinfunction "AGNDL_12") (pintype "bidirectional"))
      (node (ref "U3") (pin "17") (pinfunction "AGNDR_17") (pintype "bidirectional"))
      (node (ref "U3") (pin "19") (pinfunction "PGND_19") (pintype "bidirectional"))
      (node (ref "U3") (pin "6") (pinfunction "DGND_6") (pintype "bidirectional"))
      (node (ref "U4") (pin "7") (pinfunction "GND_7") (pintype "bidirectional"))
      (node (ref "U4") (pin "T") (pinfunction "TP_T") (pintype "bidirectional"))
      (node (ref "U5") (pin "7") (pinfunction "GND_7") (pintype "bidirectional"))
      (node (ref "U5") (pin "EP") (pinfunction "EPAD_EP") (pintype "bidirectional"))
      (node (ref "U6") (pin "7") (pinfunction "GND_7") (pintype "bidirectional"))
      (node (ref "U6") (pin "EP") (pinfunction "EPAD_EP") (pintype "bidirectional"))
      (node (ref "U8") (pin "1") (pinfunction "GND_1") (pintype "power_in"))
      (node (ref "U9") (pin "4") (pinfunction "GND_4") (pintype "power_in"))
      (node (ref "W4") (pin "1") (pinfunction "P$1_1") (pintype "bidirectional"))
    )
    (net (code "17") (name "HID0") (class "Default")
      (node (ref "J7") (pin "5") (pinfunction "S_5") (pintype "bidirectional"))
      (node (ref "U3") (pin "22") (pinfunction "HID0/MS_22") (pintype "bidirectional"))
    )
    (net (code "18") (name "HID1") (class "Default")
      (node (ref "J7") (pin "7") (pinfunction "S_7") (pintype "bidirectional"))
      (node (ref "U3") (pin "23") (pinfunction "HID1/MC_23") (pintype "bidirectional"))
    )
    (net (code "19") (name "HID2") (class "Default")
      (node (ref "J7") (pin "3") (pinfunction "S_3") (pintype "bidirectional"))
      (node (ref "U3") (pin "24") (pinfunction "HID2/MD_24") (pintype "bidirectional"))
    )
    (net (code "20") (name "MISO") (class "Default")
      (node (ref "J2") (pin "20") (pinfunction "S_20") (pintype "bidirectional"))
      (node (ref "U2") (pin "S9") (pinfunction "PA14/MISO_S9") (pintype "bidirectional"))
    )
    (net (code "21") (name "MOSI") (class "Default")
      (node (ref "J2") (pin "18") (pinfunction "S_18") (pintype "bidirectional"))
      (node (ref "U2") (pin "S10") (pinfunction "PA13/MOSI_S10") (pintype "bidirectional"))
    )
    (net (code "22") (name "NRST") (class "Default")
      (node (ref "R16") (pin "2") (pinfunction "2_2") (pintype "passive"))
      (node (ref "TP9") (pin "1") (pinfunction "P$1_1") (pintype "bidirectional"))
      (node (ref "U2") (pin "E21") (pinfunction "NRST_E21") (pintype "input"))
    )
    (net (code "23") (name "Net-(C13-Pad-)") (class "Default")
      (node (ref "C13") (pin "-") (pinfunction "-_-") (pintype "passive"))
      (node (ref "C14") (pin "-") (pinfunction "-_-") (pintype "passive"))
      (node (ref "R19") (pin "2") (pinfunction "2_2") (pintype "passive"))
    )
    (net (code "24") (name "Net-(C14-Pad+)") (class "Default")
      (node (ref "C14") (pin "+") (pinfunction "+_+") (pintype "passive"))
      (node (ref "R18") (pin "1") (pinfunction "1_1") (pintype "passive"))
      (node (ref "R29") (pin "1") (pinfunction "1_1") (pintype "passive"))
    )
    (net (code "25") (name "Net-(C16-Pad2)") (class "Default")
      (node (ref "C16") (pin "2") (pinfunction "2_2") (pintype "passive"))
      (node (ref "R21") (pin "2") (pinfunction "2_2") (pintype "passive"))
    )
    (net (code "26") (name "Net-(C17-Pad1)") (class "Default")
      (node (ref "C17") (pin "1") (pinfunction "1_1") (pintype "passive"))
      (node (ref "R20") (pin "1") (pinfunction "1_1") (pintype "passive"))
      (node (ref "R30") (pin "1") (pinfunction "1_1") (pintype "passive"))
    )
    (net (code "27") (name "Net-(J4H-S)") (class "Default")
      (node (ref "J4") (pin "7") (pinfunction "S_7") (pintype "bidirectional"))
      (node (ref "J4") (pin "8") (pinfunction "S_8") (pintype "bidirectional"))
      (node (ref "J8") (pin "1") (pinfunction "V+_1") (pintype "bidirectional"))
    )
    (net (code "28") (name "Net-(J6-5V)") (class "Default")
      (node (ref "C3") (pin "1") (pinfunction "1_1") (pintype "passive"))
      (node (ref "DA1") (pin "4") (pinfunction "4_4") (pintype "passive"))
      (node (ref "J6") (pin "1") (pinfunction "5V_1") (pintype "power_in"))
      (node (ref "L1") (pin "2") (pinfunction "2_2") (pintype "passive"))
    )
    (net (code "29") (name "Net-(TP1-P$1)") (class "Default")
      (node (ref "TP1") (pin "1") (pinfunction "P$1_1") (pintype "bidirectional"))
      (node (ref "U2") (pin "E20") (pinfunction "VBAT_E20") (pintype "power_in"))
    )
    (net (code "30") (name "Net-(TP7-P$1)") (class "Default")
      (node (ref "C13") (pin "+") (pinfunction "+_+") (pintype "passive"))
      (node (ref "C16") (pin "1") (pinfunction "1_1") (pintype "passive"))
      (node (ref "TP7") (pin "1") (pinfunction "P$1_1") (pintype "bidirectional"))
      (node (ref "U3") (pin "14") (pinfunction "VOUTL_14") (pintype "bidirectional"))
    )
    (net (code "31") (name "Net-(U2-PA9{slash}DRXD)") (class "Default")
      (node (ref "U2") (pin "S14") (pinfunction "PA9/DRXD_S14") (pintype "bidirectional"))
      (node (ref "W2") (pin "1") (pinfunction "P$1_1") (pintype "bidirectional"))
    )
    (net (code "32") (name "Net-(U2-PA10{slash}DTXD)") (class "Default")
      (node (ref "U2") (pin "S13") (pinfunction "PA10/DTXD_S13") (pintype "bidirectional"))
      (node (ref "W3") (pin "1") (pinfunction "P$1_1") (pintype "bidirectional"))
    )
    (net (code "33") (name "Net-(U3-D+)") (class "Default")
      (node (ref "R2") (pin "2") (pinfunction "2_2") (pintype "passive"))
      (node (ref "U3") (pin "9") (pinfunction "D+_9") (pintype "bidirectional"))
    )
    (net (code "34") (name "Net-(U3-D-)") (class "Default")
      (node (ref "R1") (pin "2") (pinfunction "2_2") (pintype "passive"))
      (node (ref "U3") (pin "8") (pinfunction "D-_8") (pintype "bidirectional"))
    )
    (net (code "35") (name "Net-(U3-DT)") (class "Default")
      (node (ref "R14") (pin "2") (pinfunction "2_2") (pintype "passive"))
      (node (ref "U3") (pin "3") (pinfunction "DT_3") (pintype "bidirectional"))
    )
    (net (code "36") (name "Net-(U3-VCCL)") (class "Default")
      (node (ref "C11") (pin "1") (pinfunction "1_1") (pintype "passive"))
      (node (ref "U3") (pin "13") (pinfunction "VCCL_13") (pintype "bidirectional"))
    )
    (net (code "37") (name "Net-(U3-VCCP)") (class "Default")
      (node (ref "C7") (pin "1") (pinfunction "1_1") (pintype "passive"))
      (node (ref "U3") (pin "20") (pinfunction "VCCP_20") (pintype "bidirectional"))
    )
    (net (code "38") (name "Net-(U3-VCCR)") (class "Default")
      (node (ref "C8") (pin "1") (pinfunction "1_1") (pintype "passive"))
      (node (ref "U3") (pin "16") (pinfunction "VCCR_16") (pintype "bidirectional"))
    )
    (net (code "39") (name "Net-(U3-VCOM)") (class "Default")
      (node (ref "C6") (pin "+") (pinfunction "+_+") (pintype "passive"))
      (node (ref "U3") (pin "18") (pinfunction "VCOM_18") (pintype "bidirectional"))
    )
    (net (code "40") (name "Net-(U3-VOUTR)") (class "Default")
      (node (ref "U3") (pin "15") (pinfunction "VOUTR_15") (pintype "bidirectional"))
      (node (ref "W1") (pin "1") (pinfunction "P$1_1") (pintype "bidirectional"))
    )
    (net (code "41") (name "Net-(U3-XTI)") (class "Default")
      (node (ref "C5") (pin "1") (pinfunction "1_1") (pintype "passive"))
      (node (ref "Q1") (pin "2") (pinfunction "2_2") (pintype "passive"))
      (node (ref "R13") (pin "2") (pinfunction "2_2") (pintype "passive"))
      (node (ref "U3") (pin "28") (pinfunction "XTI_28") (pintype "bidirectional"))
    )
    (net (code "42") (name "Net-(U3-XTO)") (class "Default")
      (node (ref "C4") (pin "1") (pinfunction "1_1") (pintype "passive"))
      (node (ref "Q1") (pin "1") (pinfunction "1_1") (pintype "passive"))
      (node (ref "R13") (pin "1") (pinfunction "1_1") (pintype "passive"))
      (node (ref "U3") (pin "1") (pinfunction "XTO_1") (pintype "bidirectional"))
    )
    (net (code "43") (name "Net-(U4-IN+)") (class "Default")
      (node (ref "R18") (pin "2") (pinfunction "2_2") (pintype "passive"))
      (node (ref "R29") (pin "2") (pinfunction "2_2") (pintype "passive"))
      (node (ref "U4") (pin "3") (pinfunction "IN+_3") (pintype "bidirectional"))
    )
    (net (code "44") (name "Net-(U4-IN-)") (class "Default")
      (node (ref "R20") (pin "2") (pinfunction "2_2") (pintype "passive"))
      (node (ref "R30") (pin "2") (pinfunction "2_2") (pintype "passive"))
      (node (ref "U4") (pin "4") (pinfunction "IN-_4") (pintype "bidirectional"))
    )
    (net (code "45") (name "Net-(U4-VO+)") (class "Default")
      (node (ref "L6") (pin "1") (pinfunction "1_1") (pintype "passive"))
      (node (ref "U4") (pin "5") (pinfunction "VO+_5") (pintype "bidirectional"))
    )
    (net (code "46") (name "Net-(U4-VO-)") (class "Default")
      (node (ref "L7") (pin "1") (pinfunction "1_1") (pintype "passive"))
      (node (ref "U4") (pin "8") (pinfunction "VO-_8") (pintype "bidirectional"))
    )
    (net (code "47") (name "Net-(U5-BST)") (class "Default")
      (node (ref "C21") (pin "1") (pinfunction "1_1") (pintype "passive"))
      (node (ref "U5") (pin "1") (pinfunction "BST_1") (pintype "bidirectional"))
    )
    (net (code "48") (name "Net-(U5-SW)") (class "Default")
      (node (ref "C21") (pin "2") (pinfunction "2_2") (pintype "passive"))
      (node (ref "D1") (pin "K") (pinfunction "K_K") (pintype "passive"))
      (node (ref "L3") (pin "1") (pinfunction "1_1") (pintype "passive"))
      (node (ref "U5") (pin "8") (pinfunction "SW_8") (pintype "bidirectional"))
    )
    (net (code "49") (name "Net-(U6-BST)") (class "Default")
      (node (ref "C24") (pin "1") (pinfunction "1_1") (pintype "passive"))
      (node (ref "U6") (pin "1") (pinfunction "BST_1") (pintype "bidirectional"))
    )
    (net (code "50") (name "Net-(U6-SW)") (class "Default")
      (node (ref "C24") (pin "2") (pinfunction "2_2") (pintype "passive"))
      (node (ref "D2") (pin "K") (pinfunction "K_K") (pintype "passive"))
      (node (ref "L2") (pin "1") (pinfunction "1_1") (pintype "passive"))
      (node (ref "U6") (pin "8") (pinfunction "SW_8") (pintype "bidirectional"))
    )
    (net (code "51") (name "Net-(U8-~{RST})") (class "Default")
      (node (ref "R16") (pin "1") (pinfunction "1_1") (pintype "passive"))
      (node (ref "U8") (pin "2") (pinfunction "~{RST}_2") (pintype "open_collector"))
    )
    (net (code "52") (name "PC18{slash}PWM0") (class "Default")
      (node (ref "J2") (pin "10") (pinfunction "S_10") (pintype "bidirectional"))
      (node (ref "U2") (pin "N20") (pinfunction "PC18/PWM0_N20") (pintype "bidirectional"))
    )
    (net (code "53") (name "PC19{slash}PWM1") (class "Default")
      (node (ref "J2") (pin "12") (pinfunction "S_12") (pintype "bidirectional"))
      (node (ref "U2") (pin "N21") (pinfunction "PC19/PWM1_N21") (pintype "bidirectional"))
    )
    (net (code "54") (name "PC20{slash}PWM2") (class "Default")
      (node (ref "J2") (pin "11") (pinfunction "S_11") (pintype "bidirectional"))
      (node (ref "U2") (pin "N22") (pinfunction "PC20/PWM2_N22") (pintype "bidirectional"))
    )
    (net (code "55") (name "PC22{slash}TXD3") (class "Default")
      (node (ref "J2") (pin "13") (pinfunction "S_13") (pintype "bidirectional"))
      (node (ref "U2") (pin "E2") (pinfunction "PC22/TXD3_E2") (pintype "bidirectional"))
    )
    (net (code "56") (name "PC23{slash}RXD3") (class "Default")
      (node (ref "J2") (pin "15") (pinfunction "S_15") (pintype "bidirectional"))
      (node (ref "U2") (pin "E3") (pinfunction "PC23/RXD3_E3") (pintype "bidirectional"))
    )
    (net (code "57") (name "PC24{slash}RTS3") (class "Default")
      (node (ref "J2") (pin "17") (pinfunction "S_17") (pintype "bidirectional"))
      (node (ref "U2") (pin "E4") (pinfunction "PC24/RTS3_E4") (pintype "bidirectional"))
    )
    (net (code "58") (name "PC25{slash}CTS3") (class "Default")
      (node (ref "J2") (pin "19") (pinfunction "S_19") (pintype "bidirectional"))
      (node (ref "U2") (pin "E5") (pinfunction "PC25/CTS3_E5") (pintype "bidirectional"))
    )
    (net (code "59") (name "SCL0") (class "Default")
      (node (ref "J2") (pin "8") (pinfunction "S_8") (pintype "bidirectional"))
      (node (ref "J4") (pin "2") (pinfunction "S_2") (pintype "bidirectional"))
      (node (ref "R4") (pin "2") (pinfunction "2_2") (pintype "passive"))
      (node (ref "U2") (pin "W18") (pinfunction "PA31/SCL0_W18") (pintype "bidirectional"))
      (node (ref "U9") (pin "2") (pinfunction "SCL_2") (pintype "bidirectional"))
    )
    (net (code "60") (name "SDA0") (class "Default")
      (node (ref "J2") (pin "6") (pinfunction "S_6") (pintype "bidirectional"))
      (node (ref "J4") (pin "4") (pinfunction "S_4") (pintype "bidirectional"))
      (node (ref "R3") (pin "2") (pinfunction "2_2") (pintype "passive"))
      (node (ref "U2") (pin "W17") (pinfunction "PA30/SDA0_W17") (pintype "bidirectional"))
      (node (ref "U9") (pin "1") (pinfunction "SDA_1") (pintype "bidirectional"))
    )
    (net (code "61") (name "SD_CLK") (class "Default")
      (node (ref "J3") (pin "5") (pinfunction "CLK_5") (pintype "input"))
      (node (ref "U2") (pin "S6") (pinfunction "PA17/SD_CK_S6") (pintype "bidirectional"))
    )
    (net (code "62") (name "SD_CMD") (class "Default")
      (node (ref "J3") (pin "3") (pinfunction "CMD_3") (pintype "input"))
      (node (ref "U2") (pin "S7") (pinfunction "PA16/SD_CDA_S7") (pintype "bidirectional"))
    )
    (net (code "63") (name "SD_DAT0") (class "Default")
      (node (ref "J3") (pin "7") (pinfunction "DAT0_7") (pintype "bidirectional"))
      (node (ref "U2") (pin "S8") (pinfunction "PA15/SD_DA0_S8") (pintype "bidirectional"))
    )
    (net (code "64") (name "SD_DAT1") (class "Default")
      (node (ref "J3") (pin "8") (pinfunction "DAT1_8") (pintype "bidirectional"))
      (node (ref "U2") (pin "S5") (pinfunction "PA18/SD_DA1_S5") (pintype "bidirectional"))
    )
    (net (code "65") (name "SD_DAT2") (class "Default")
      (node (ref "J3") (pin "1") (pinfunction "DAT2_1") (pintype "bidirectional"))
      (node (ref "U2") (pin "S4") (pinfunction "PA19/SD_DA2_S4") (pintype "bidirectional"))
    )
    (net (code "66") (name "SD_DAT3") (class "Default")
      (node (ref "J3") (pin "2") (pinfunction "CD/DAT3_2") (pintype "bidirectional"))
      (node (ref "U2") (pin "S3") (pinfunction "PA20/SD_DA3_S3") (pintype "bidirectional"))
    )
    (net (code "67") (name "SPCK") (class "Default")
      (node (ref "J2") (pin "16") (pinfunction "S_16") (pintype "bidirectional"))
      (node (ref "U2") (pin "S11") (pinfunction "PA12/SPCK_S11") (pintype "bidirectional"))
    )
    (net (code "68") (name "SPI_CS0") (class "Default")
      (node (ref "J2") (pin "14") (pinfunction "S_14") (pintype "bidirectional"))
      (node (ref "U2") (pin "S12") (pinfunction "PA11/NPCS0_S12") (pintype "bidirectional"))
    )
    (net (code "69") (name "SPK+") (class "Default")
      (node (ref "C33") (pin "1") (pinfunction "1_1") (pintype "passive"))
      (node (ref "J7") (pin "10") (pinfunction "S_10") (pintype "bidirectional"))
      (node (ref "L6") (pin "2") (pinfunction "2_2") (pintype "passive"))
    )
    (net (code "70") (name "SPK-") (class "Default")
      (node (ref "C32") (pin "1") (pinfunction "1_1") (pintype "passive"))
      (node (ref "J7") (pin "9") (pinfunction "S_9") (pintype "bidirectional"))
      (node (ref "L7") (pin "2") (pinfunction "2_2") (pintype "passive"))
    )
    (net (code "71") (name "USBA_5V") (class "Default")
      (node (ref "C1") (pin "1") (pinfunction "1_1") (pintype "passive"))
      (node (ref "C2") (pin "1") (pinfunction "1_1") (pintype "passive"))
      (node (ref "L1") (pin "1") (pinfunction "1_1") (pintype "passive"))
      (node (ref "U1") (pin "8") (pinfunction "OUT1_8") (pintype "power_in"))
    )
    (net (code "72") (name "USBA_D+") (class "Default")
      (node (ref "DA1") (pin "2") (pinfunction "2_2") (pintype "passive"))
      (node (ref "J6") (pin "3") (pinfunction "D+_3") (pintype "bidirectional"))
      (node (ref "U2") (pin "E19") (pinfunction "USBAP_E19") (pintype "bidirectional"))
    )
    (net (code "73") (name "USBA_D-") (class "Default")
      (node (ref "DA1") (pin "3") (pinfunction "3_3") (pintype "passive"))
      (node (ref "J6") (pin "2") (pinfunction "D-_2") (pintype "bidirectional"))
      (node (ref "U2") (pin "E18") (pinfunction "USBAN_E18") (pintype "bidirectional"))
    )
    (net (code "74") (name "USBB_5V") (class "Default")
      (node (ref "J1") (pin "1") (pinfunction "S_1") (pintype "bidirectional"))
      (node (ref "U1") (pin "5") (pinfunction "OUT2_5") (pintype "power_in"))
    )
    (net (code "75") (name "USBB_D+") (class "Default")
      (node (ref "J1") (pin "2") (pinfunction "S_2") (pintype "bidirectional"))
      (node (ref "U2") (pin "E16") (pinfunction "USBBP_E16") (pintype "bidirectional"))
    )
    (net (code "76") (name "USBB_D-") (class "Default")
      (node (ref "J1") (pin "3") (pinfunction "S_3") (pintype "bidirectional"))
      (node (ref "U2") (pin "E15") (pinfunction "USBBN_E15") (pintype "bidirectional"))
    )
    (net (code "77") (name "USBC_D+") (class "Default")
      (node (ref "R15") (pin "1") (pinfunction "1_1") (pintype "passive"))
      (node (ref "R2") (pin "1") (pinfunction "1_1") (pintype "passive"))
      (node (ref "U2") (pin "E12") (pinfunction "USBCP_E12") (pintype "bidirectional"))
    )
    (net (code "78") (name "USBC_D-") (class "Default")
      (node (ref "R1") (pin "1") (pinfunction "1_1") (pintype "passive"))
      (node (ref "U2") (pin "E13") (pinfunction "USBCN_E13") (pintype "bidirectional"))
    )
    (net (code "79") (name "USB_EN1") (class "Default")
      (node (ref "R8") (pin "1") (pinfunction "1_1") (pintype "passive"))
      (node (ref "U1") (pin "1") (pinfunction "~{EN1}_1") (pintype "input"))
      (node (ref "U2") (pin "W13") (pinfunction "PA26_W13") (pintype "bidirectional"))
    )
    (net (code "80") (name "USB_EN2") (class "Default")
      (node (ref "R6") (pin "1") (pinfunction "1_1") (pintype "passive"))
      (node (ref "U1") (pin "4") (pinfunction "~{EN2}_4") (pintype "input"))
      (node (ref "U2") (pin "W16") (pinfunction "PA29_W16") (pintype "bidirectional"))
    )
    (net (code "81") (name "USB_FLAG1") (class "Default")
      (node (ref "R7") (pin "1") (pinfunction "1_1") (pintype "passive"))
      (node (ref "U1") (pin "2") (pinfunction "FLAG1_2") (pintype "output"))
      (node (ref "U2") (pin "W14") (pinfunction "PA27_W14") (pintype "bidirectional"))
    )
    (net (code "82") (name "USB_FLAG2") (class "Default")
      (node (ref "R5") (pin "1") (pinfunction "1_1") (pintype "passive"))
      (node (ref "U1") (pin "3") (pinfunction "FLAG2_3") (pintype "output"))
      (node (ref "U2") (pin "W15") (pinfunction "PA28_W15") (pintype "bidirectional"))
    )
    (net (code "83") (name "V_AUX_ON") (class "Default")
      (node (ref "J4") (pin "1") (pinfunction "S_1") (pintype "bidirectional"))
      (node (ref "U2") (pin "W9") (pinfunction "PA22_W9") (pintype "bidirectional"))
    )
    (net (code "84") (name "unconnected-(J3-PadDC)") (class "Default")
      (node (ref "J3") (pin "DC") (pinfunction "DC_DC") (pintype "passive"))
    )
    (net (code "85") (name "unconnected-(J3-PadDT)") (class "Default")
      (node (ref "J3") (pin "DT") (pinfunction "DT_DT") (pintype "bidirectional"))
    )
    (net (code "86") (name "unconnected-(J7C-S-Pad2)") (class "Default")
      (node (ref "J7") (pin "2") (pinfunction "S_2") (pintype "bidirectional"))
    )
    (net (code "87") (name "unconnected-(J9-S-Pad1)") (class "Default")
      (node (ref "J9") (pin "1") (pinfunction "S_1") (pintype "bidirectional"))
    )
    (net (code "88") (name "unconnected-(J10-S-Pad1)") (class "Default")
      (node (ref "J10") (pin "1") (pinfunction "S_1") (pintype "bidirectional"))
    )
    (net (code "89") (name "unconnected-(U2-ADVREF-PadW19)") (class "Default")
      (node (ref "U2") (pin "W19") (pinfunction "ADVREF_W19") (pintype "bidirectional"))
    )
    (net (code "90") (name "unconnected-(U2-PA0{slash}TXD0-PadS23)") (class "Default")
      (node (ref "U2") (pin "S23") (pinfunction "PA0/TXD0_S23") (pintype "bidirectional"))
    )
    (net (code "91") (name "unconnected-(U2-PA1{slash}RXD0-PadS22)") (class "Default")
      (node (ref "U2") (pin "S22") (pinfunction "PA1/RXD0_S22") (pintype "bidirectional"))
    )
    (net (code "92") (name "unconnected-(U2-PA2{slash}RTS0-PadS21)") (class "Default")
      (node (ref "U2") (pin "S21") (pinfunction "PA2/RTS0_S21") (pintype "bidirectional"))
    )
    (net (code "93") (name "unconnected-(U2-PA3{slash}CTS0-PadS20)") (class "Default")
      (node (ref "U2") (pin "S20") (pinfunction "PA3/CTS0_S20") (pintype "bidirectional"))
    )
    (net (code "94") (name "unconnected-(U2-PA4-PadS19)") (class "Default")
      (node (ref "U2") (pin "S19") (pinfunction "PA4_S19") (pintype "bidirectional"))
    )
    (net (code "95") (name "unconnected-(U2-PA5{slash}TXD1-PadS18)") (class "Default")
      (node (ref "U2") (pin "S18") (pinfunction "PA5/TXD1_S18") (pintype "bidirectional"))
    )
    (net (code "96") (name "unconnected-(U2-PA6{slash}RXD1-PadS17)") (class "Default")
      (node (ref "U2") (pin "S17") (pinfunction "PA6/RXD1_S17") (pintype "bidirectional"))
    )
    (net (code "97") (name "unconnected-(U2-PA7{slash}TXD2-PadS16)") (class "Default")
      (node (ref "U2") (pin "S16") (pinfunction "PA7/TXD2_S16") (pintype "bidirectional"))
    )
    (net (code "98") (name "unconnected-(U2-PA8{slash}RXD2-PadS15)") (class "Default")
      (node (ref "U2") (pin "S15") (pinfunction "PA8/RXD2_S15") (pintype "bidirectional"))
    )
    (net (code "99") (name "unconnected-(U2-PA21{slash}1WIRE-PadS2)") (class "Default")
      (node (ref "U2") (pin "S2") (pinfunction "PA21/1WIRE_S2") (pintype "bidirectional"))
    )
    (net (code "100") (name "unconnected-(U2-PA23-PadW10)") (class "Default")
      (node (ref "U2") (pin "W10") (pinfunction "PA23_W10") (pintype "bidirectional"))
    )
    (net (code "101") (name "unconnected-(U2-PA24-PadW11)") (class "Default")
      (node (ref "U2") (pin "W11") (pinfunction "PA24_W11") (pintype "bidirectional"))
    )
    (net (code "102") (name "unconnected-(U2-PA25-PadW12)") (class "Default")
      (node (ref "U2") (pin "W12") (pinfunction "PA25_W12") (pintype "bidirectional"))
    )
    (net (code "103") (name "unconnected-(U2-PB11{slash}AD0-PadW20)") (class "Default")
      (node (ref "U2") (pin "W20") (pinfunction "PB11/AD0_W20") (pintype "bidirectional"))
    )
    (net (code "104") (name "unconnected-(U2-PB12{slash}AD1-PadW21)") (class "Default")
      (node (ref "U2") (pin "W21") (pinfunction "PB12/AD1_W21") (pintype "bidirectional"))
    )
    (net (code "105") (name "unconnected-(U2-PB13{slash}AD2-PadW22)") (class "Default")
      (node (ref "U2") (pin "W22") (pinfunction "PB13/AD2_W22") (pintype "bidirectional"))
    )
    (net (code "106") (name "unconnected-(U2-PB14{slash}AD3-PadW23)") (class "Default")
      (node (ref "U2") (pin "W23") (pinfunction "PB14/AD3_W23") (pintype "bidirectional"))
    )
    (net (code "107") (name "unconnected-(U2-PC0{slash}SDA1-PadN2)") (class "Default")
      (node (ref "U2") (pin "N2") (pinfunction "PC0/SDA1_N2") (pintype "bidirectional"))
    )
    (net (code "108") (name "unconnected-(U2-PC1{slash}SCL1-PadN3)") (class "Default")
      (node (ref "U2") (pin "N3") (pinfunction "PC1/SCL1_N3") (pintype "bidirectional"))
    )
    (net (code "109") (name "unconnected-(U2-PC2-PadN4)") (class "Default")
      (node (ref "U2") (pin "N4") (pinfunction "PC2_N4") (pintype "bidirectional"))
    )
    (net (code "110") (name "unconnected-(U2-PC3-PadN5)") (class "Default")
      (node (ref "U2") (pin "N5") (pinfunction "PC3_N5") (pintype "bidirectional"))
    )
    (net (code "111") (name "unconnected-(U2-PC4-PadN6)") (class "Default")
      (node (ref "U2") (pin "N6") (pinfunction "PC4_N6") (pintype "bidirectional"))
    )
    (net (code "112") (name "unconnected-(U2-PC5-PadN7)") (class "Default")
      (node (ref "U2") (pin "N7") (pinfunction "PC5_N7") (pintype "bidirectional"))
    )
    (net (code "113") (name "unconnected-(U2-PC6-PadN8)") (class "Default")
      (node (ref "U2") (pin "N8") (pinfunction "PC6_N8") (pintype "bidirectional"))
    )
    (net (code "114") (name "unconnected-(U2-PC7-PadN9)") (class "Default")
      (node (ref "U2") (pin "N9") (pinfunction "PC7_N9") (pintype "bidirectional"))
    )
    (net (code "115") (name "unconnected-(U2-PC8{slash}UTXD0-PadN10)") (class "Default")
      (node (ref "U2") (pin "N10") (pinfunction "PC8/UTXD0_N10") (pintype "bidirectional"))
    )
    (net (code "116") (name "unconnected-(U2-PC9{slash}URXD0-PadN11)") (class "Default")
      (node (ref "U2") (pin "N11") (pinfunction "PC9/URXD0_N11") (pintype "bidirectional"))
    )
    (net (code "117") (name "unconnected-(U2-PC10-PadN12)") (class "Default")
      (node (ref "U2") (pin "N12") (pinfunction "PC10_N12") (pintype "bidirectional"))
    )
    (net (code "118") (name "unconnected-(U2-PC11-PadN13)") (class "Default")
      (node (ref "U2") (pin "N13") (pinfunction "PC11_N13") (pintype "bidirectional"))
    )
    (net (code "119") (name "unconnected-(U2-PC12-PadN14)") (class "Default")
      (node (ref "U2") (pin "N14") (pinfunction "PC12_N14") (pintype "bidirectional"))
    )
    (net (code "120") (name "unconnected-(U2-PC13-PadN15)") (class "Default")
      (node (ref "U2") (pin "N15") (pinfunction "PC13_N15") (pintype "bidirectional"))
    )
    (net (code "121") (name "unconnected-(U2-PC14-PadN16)") (class "Default")
      (node (ref "U2") (pin "N16") (pinfunction "PC14_N16") (pintype "bidirectional"))
    )
    (net (code "122") (name "unconnected-(U2-PC15-PadN17)") (class "Default")
      (node (ref "U2") (pin "N17") (pinfunction "PC15_N17") (pintype "bidirectional"))
    )
    (net (code "123") (name "unconnected-(U2-PC16{slash}UTXD1-PadN18)") (class "Default")
      (node (ref "U2") (pin "N18") (pinfunction "PC16/UTXD1_N18") (pintype "bidirectional"))
    )
    (net (code "124") (name "unconnected-(U2-PC17{slash}URXD1-PadN19)") (class "Default")
      (node (ref "U2") (pin "N19") (pinfunction "PC17/URXD1_N19") (pintype "bidirectional"))
    )
    (net (code "125") (name "unconnected-(U2-PC21{slash}PWM3-PadN23)") (class "Default")
      (node (ref "U2") (pin "N23") (pinfunction "PC21/PWM3_N23") (pintype "bidirectional"))
    )
    (net (code "126") (name "unconnected-(U2-PC26-PadE6)") (class "Default")
      (node (ref "U2") (pin "E6") (pinfunction "PC26_E6") (pintype "bidirectional"))
    )
    (net (code "127") (name "unconnected-(U2-PC27{slash}RTS1-PadE7)") (class "Default")
      (node (ref "U2") (pin "E7") (pinfunction "PC27/RTS1_E7") (pintype "bidirectional"))
    )
    (net (code "128") (name "unconnected-(U2-PC28{slash}CTS1-PadE8)") (class "Default")
      (node (ref "U2") (pin "E8") (pinfunction "PC28/CTS1_E8") (pintype "bidirectional"))
    )
    (net (code "129") (name "unconnected-(U2-PC29-PadE9)") (class "Default")
      (node (ref "U2") (pin "E9") (pinfunction "PC29_E9") (pintype "bidirectional"))
    )
    (net (code "130") (name "unconnected-(U2-PC30-PadE10)") (class "Default")
      (node (ref "U2") (pin "E10") (pinfunction "PC30_E10") (pintype "bidirectional"))
    )
    (net (code "131") (name "unconnected-(U2-PC31-PadE11)") (class "Default")
      (node (ref "U2") (pin "E11") (pinfunction "PC31_E11") (pintype "bidirectional"))
    )
    (net (code "132") (name "unconnected-(U2-SHDN-PadE22)") (class "Default")
      (node (ref "U2") (pin "E22") (pinfunction "SHDN_E22") (pintype "bidirectional"))
    )
    (net (code "133") (name "unconnected-(U2-WKUP-PadE23)") (class "Default")
      (node (ref "U2") (pin "E23") (pinfunction "WKUP_E23") (pintype "bidirectional"))
    )
    (net (code "134") (name "unconnected-(U3-CK-Pad2)") (class "Default")
      (node (ref "U3") (pin "2") (pinfunction "CK_2") (pintype "bidirectional"))
    )
    (net (code "135") (name "unconnected-(U5-PGOOD-Pad4)") (class "Default")
      (node (ref "U5") (pin "4") (pinfunction "PGOOD_4") (pintype "bidirectional"))
    )
    (net (code "136") (name "unconnected-(U6-PGOOD-Pad4)") (class "Default")
      (node (ref "U6") (pin "4") (pinfunction "PGOOD_4") (pintype "bidirectional"))
    )
    (net (code "137") (name "unconnected-(U8-~{MR}-Pad3)") (class "Default")
      (node (ref "U8") (pin "3") (pinfunction "~{MR}_3") (pintype "input"))
    )
    (net (code "138") (name "unconnected-(U9-ALERT-Pad3)") (class "Default")
      (node (ref "U9") (pin "3") (pinfunction "ALERT_3") (pintype "bidirectional"))
    )
  )
)
